# main.net
KiCad netlist of a schematic drawn in EAGLE
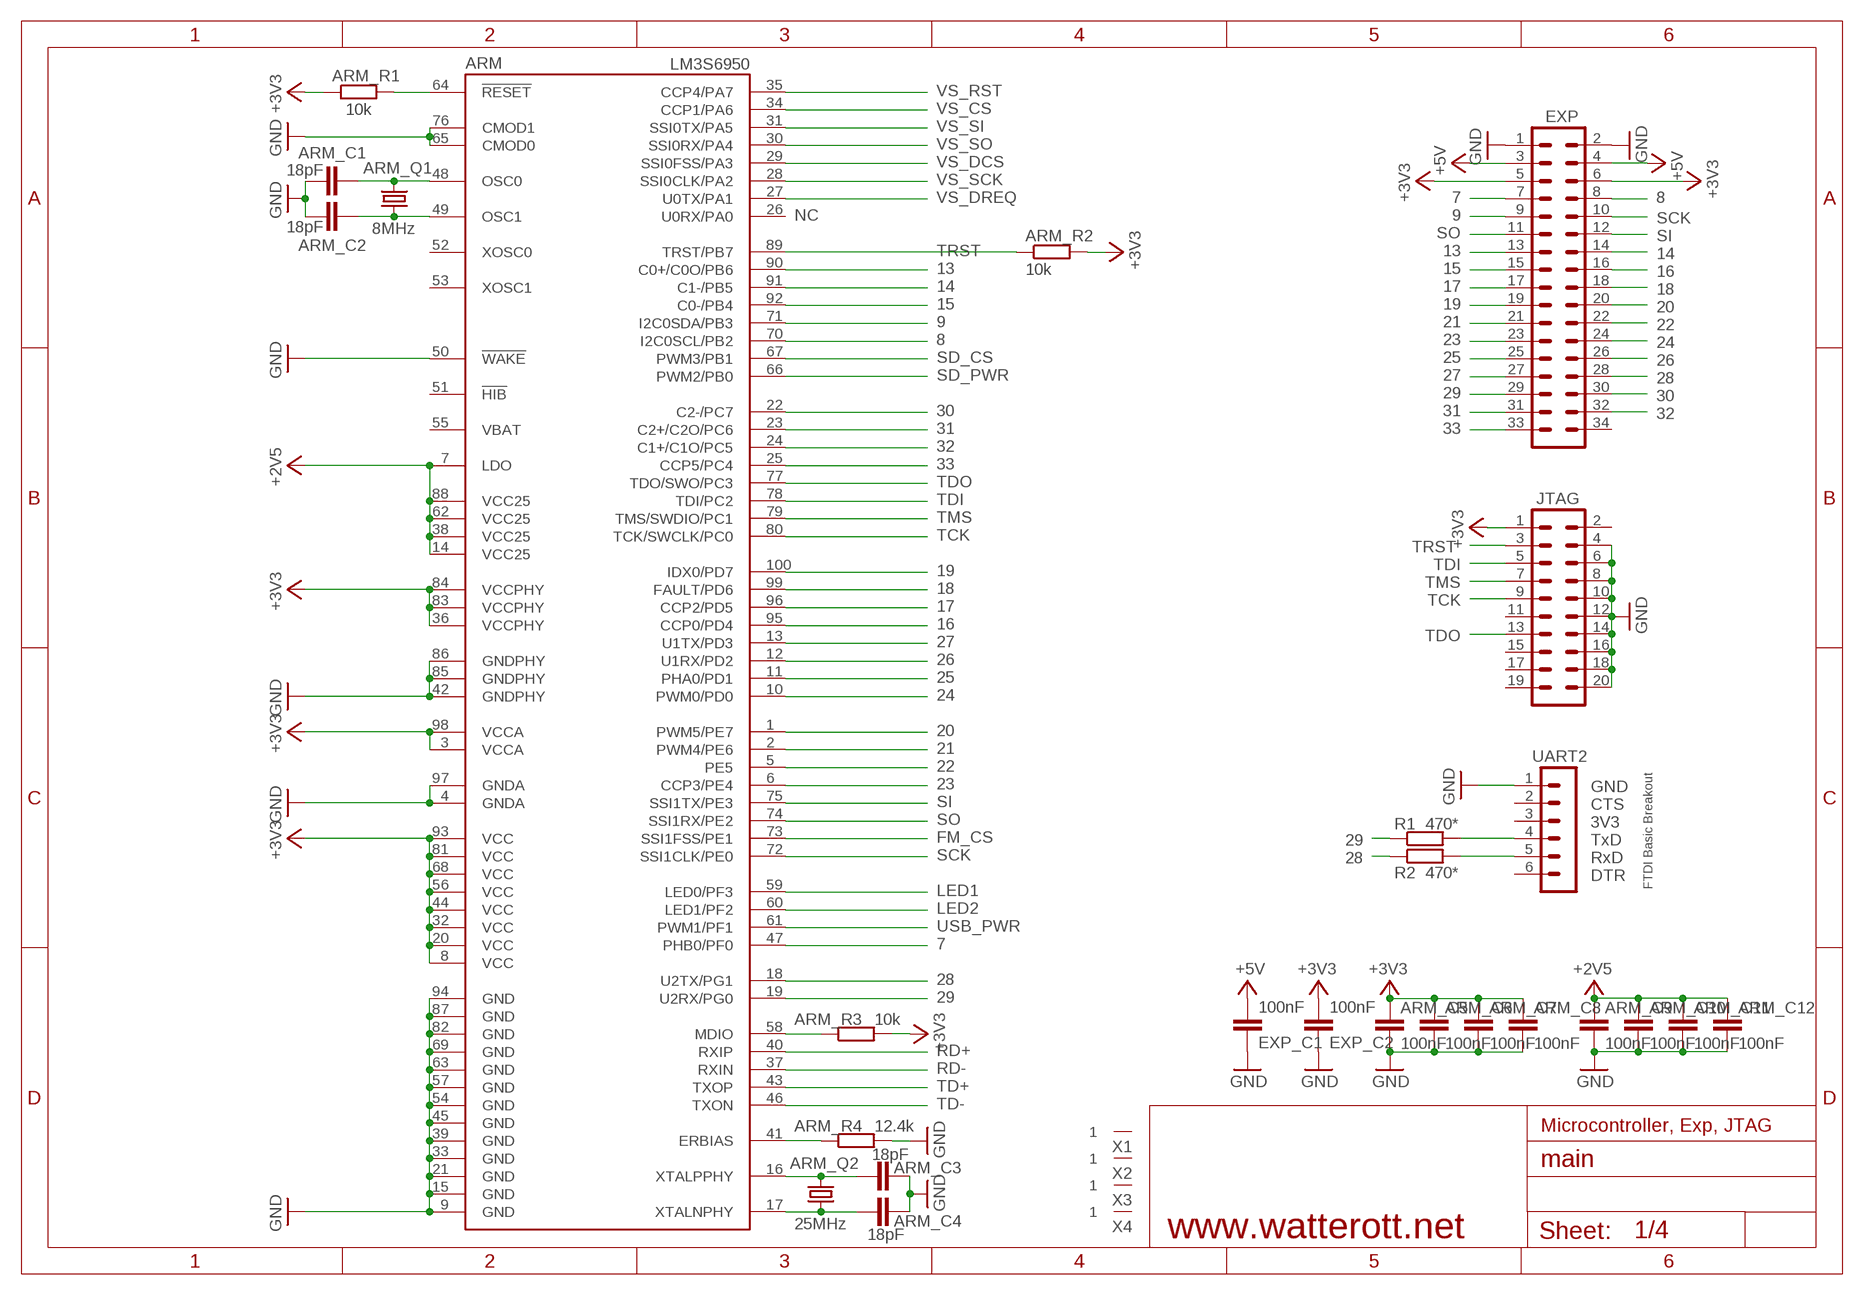
[diagram p0: schematic, sheet 1]
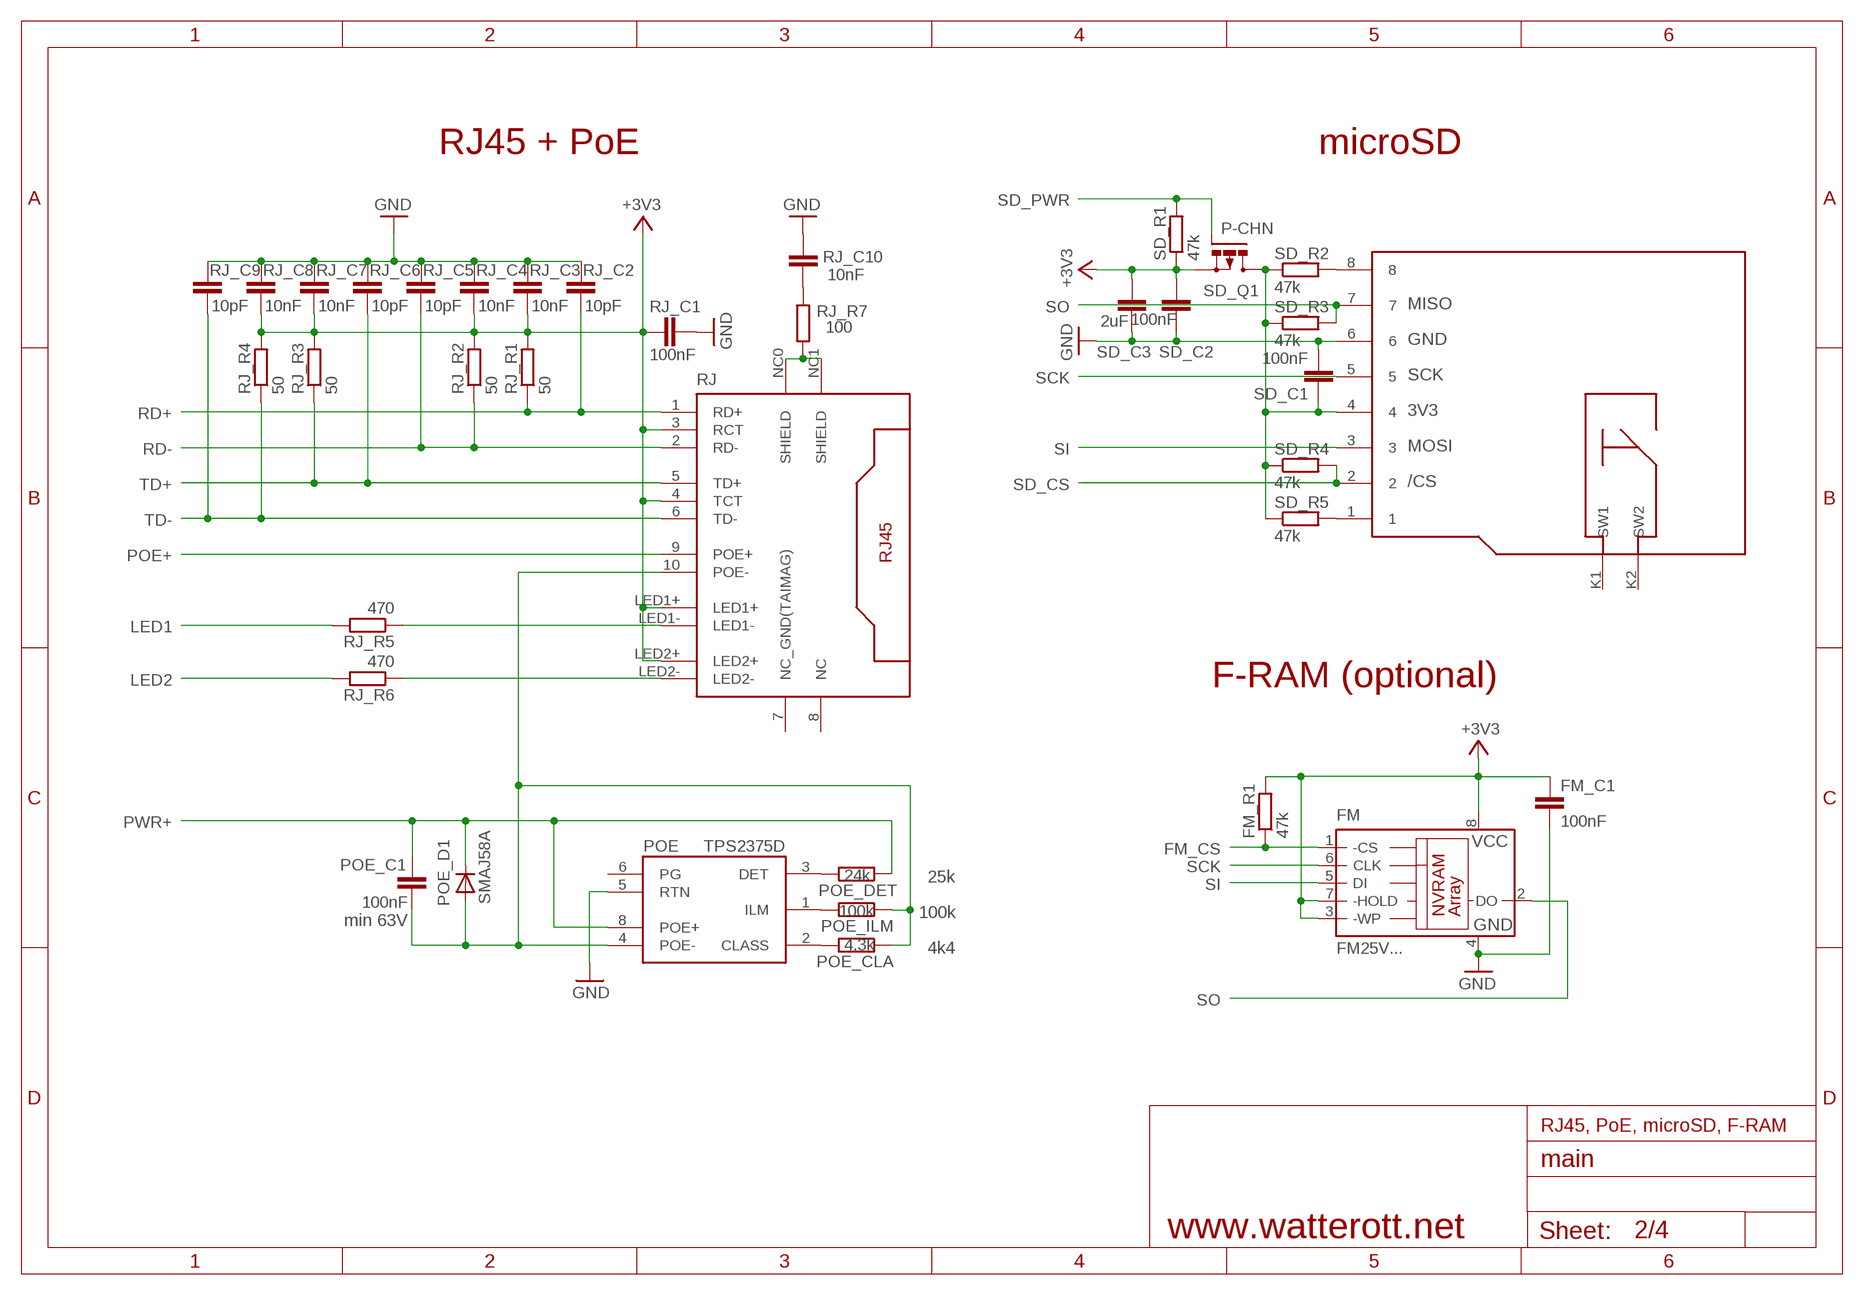
[diagram p1: schematic, sheet 2]
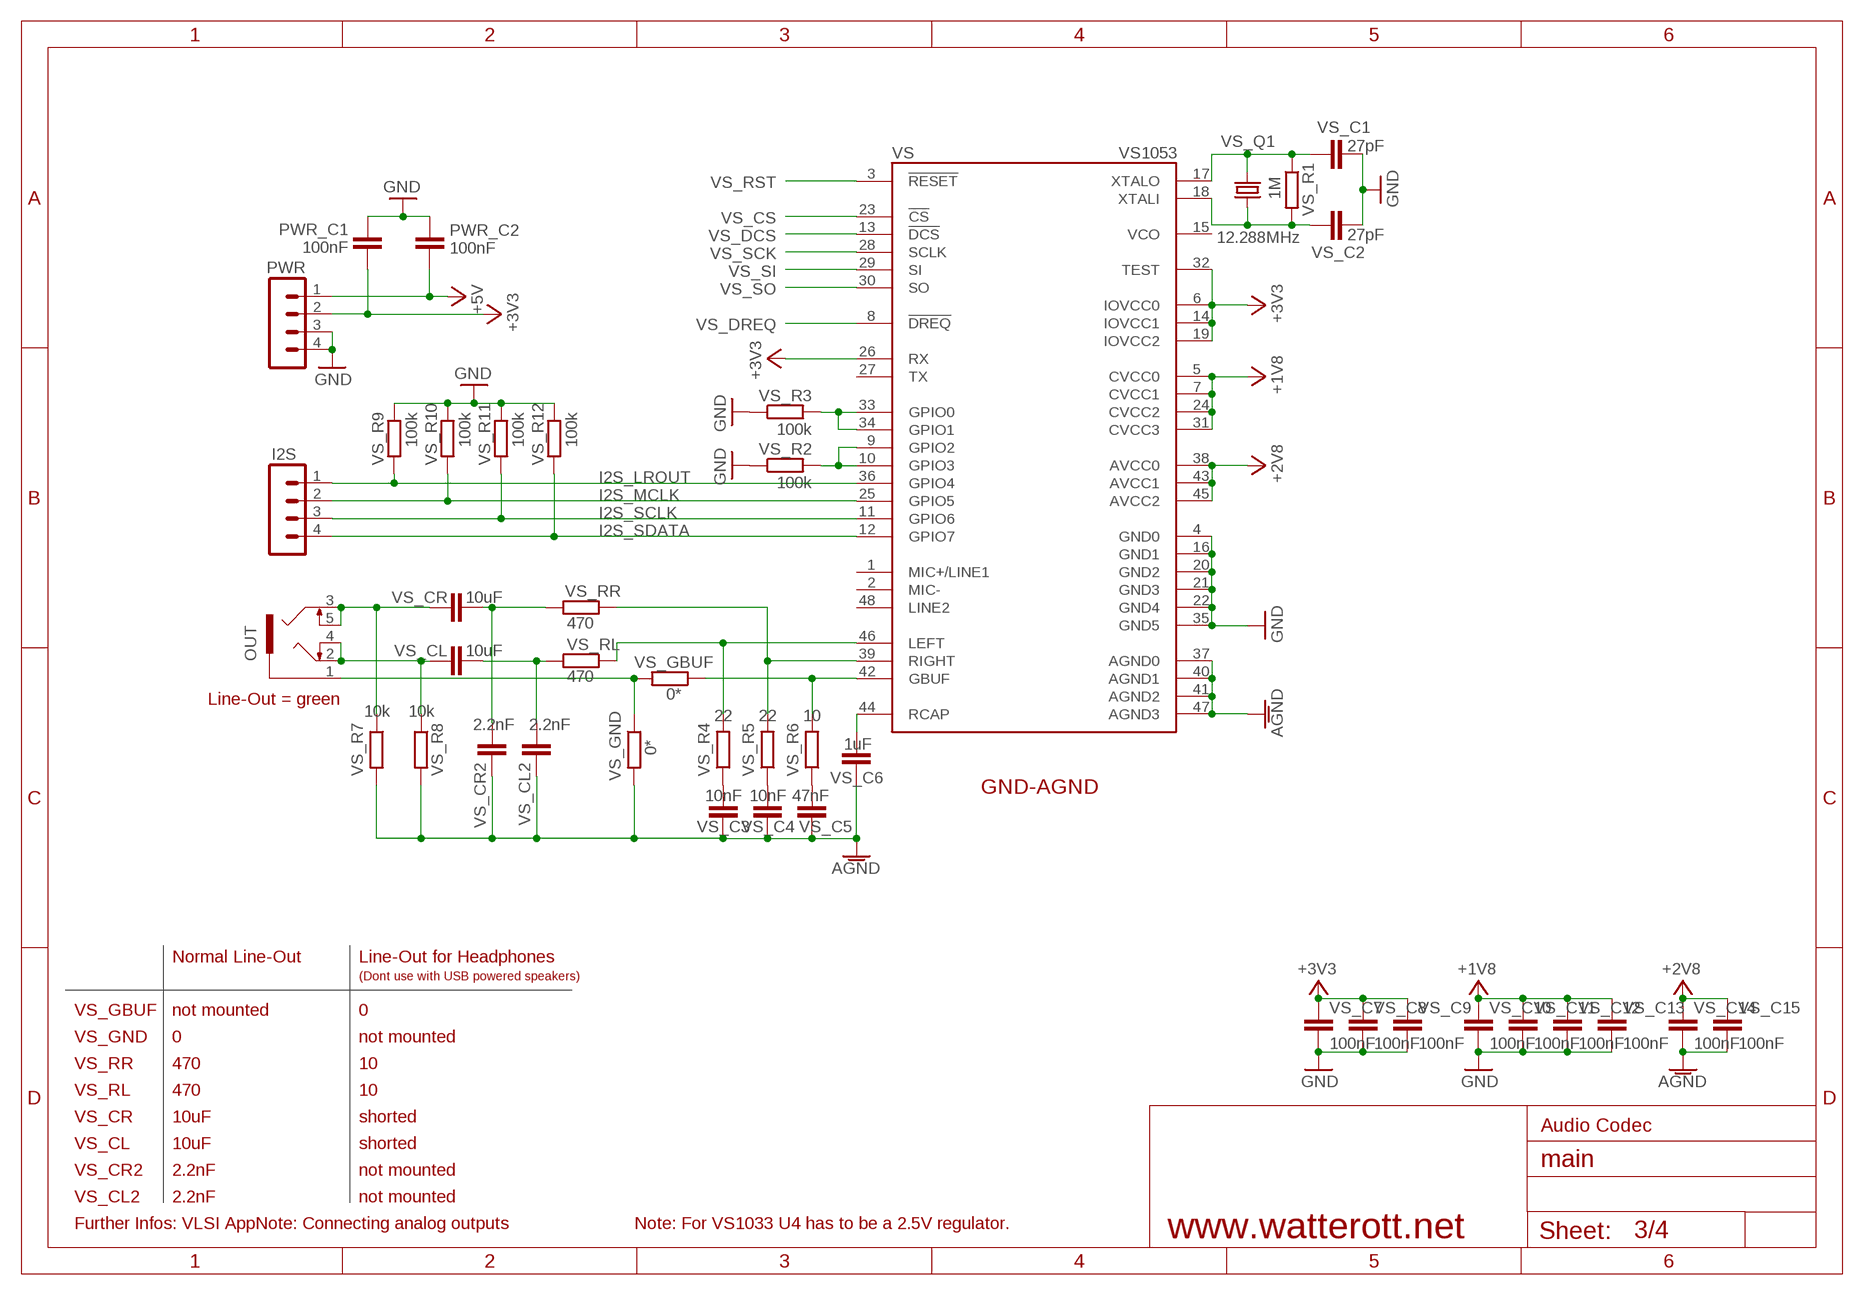
[diagram p2: schematic, sheet 3]
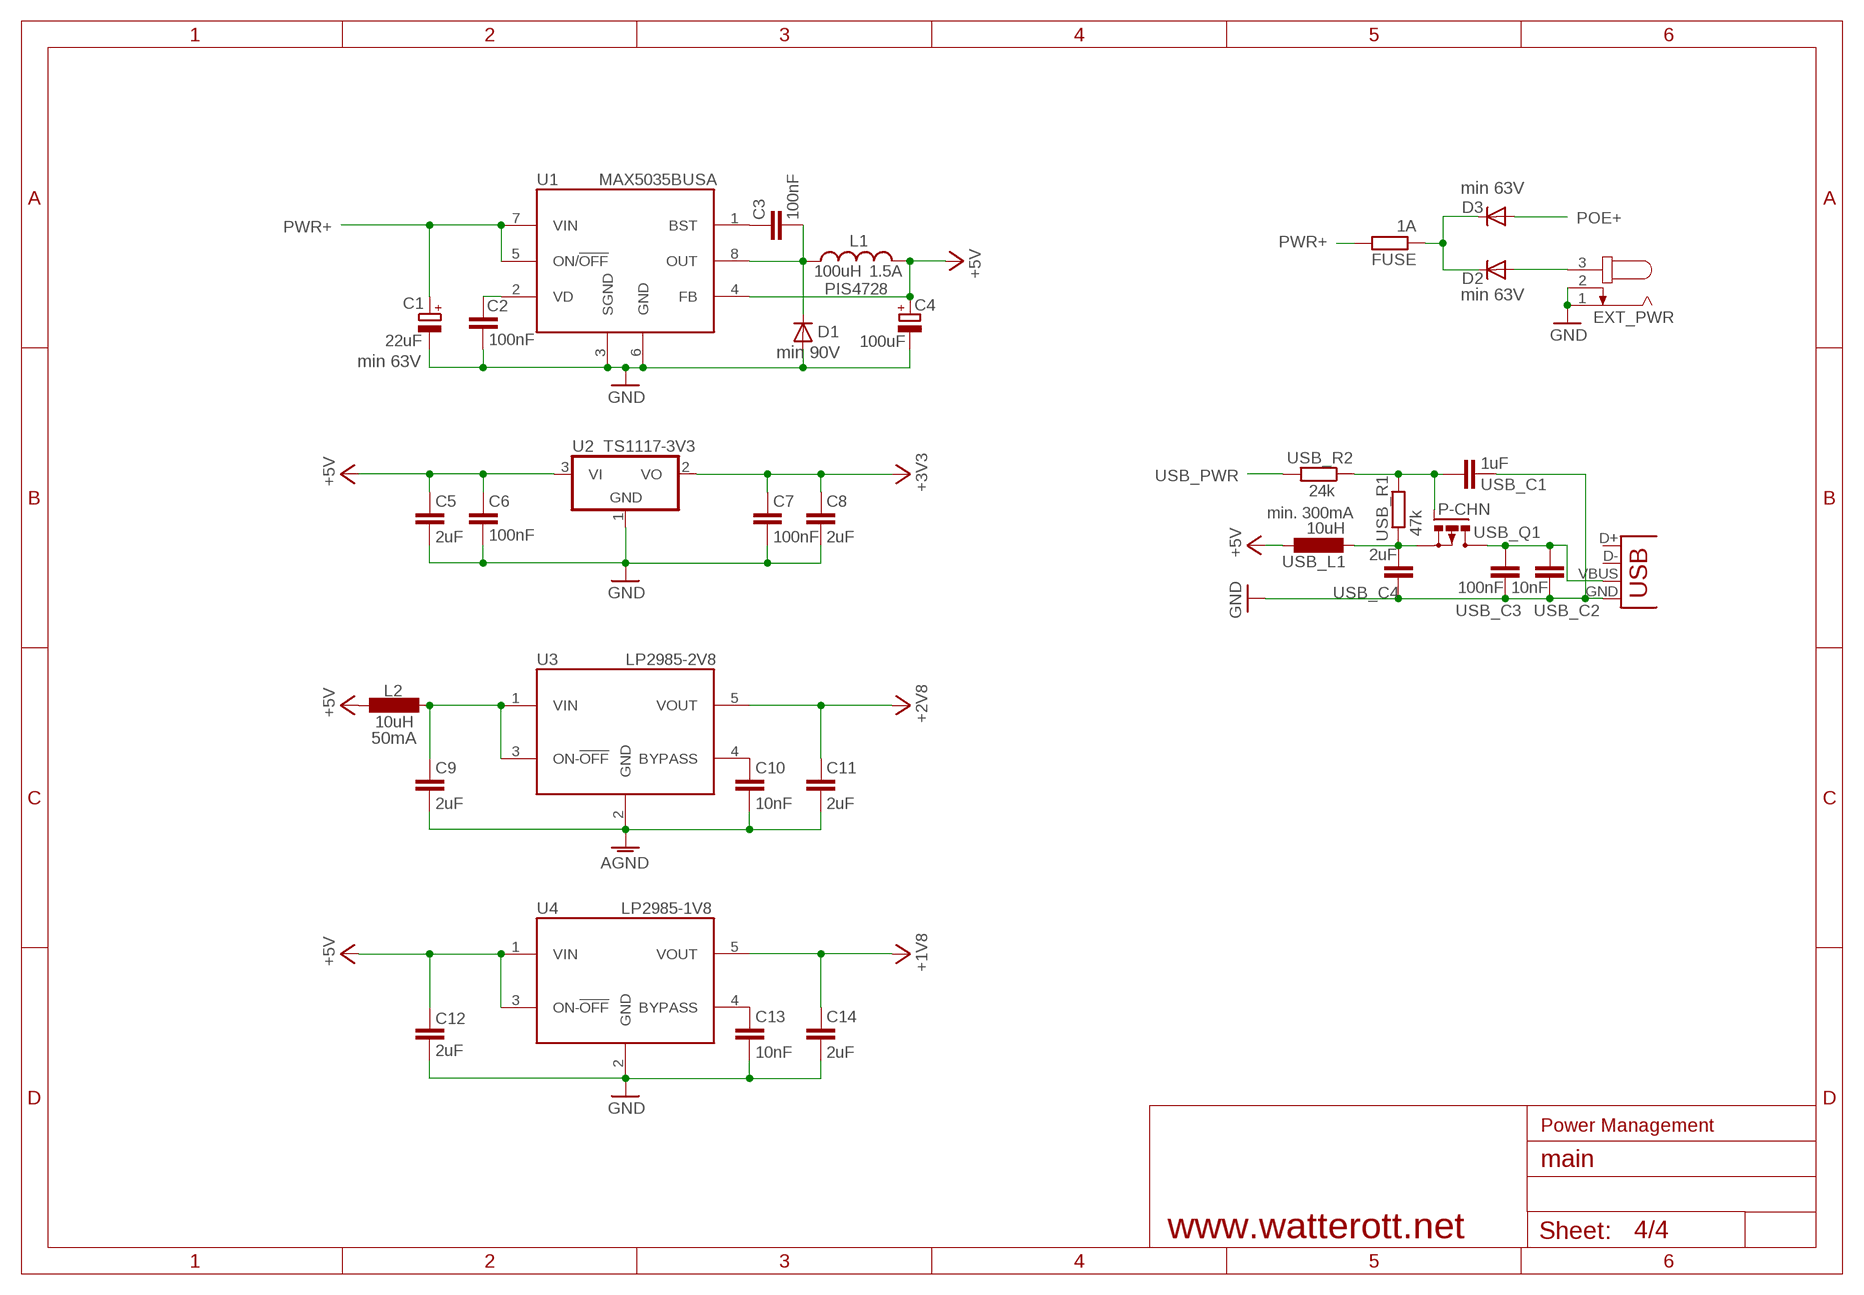
[diagram p3: schematic, sheet 4]

(export (version "E")
  (design (tool "Eeschema 10.0.6"))
  (components
    (comp (ref "I2S")
      (value "MA04-1")
      (footprint "eagle-import:MA04-1")
      (libsource (lib "eagle-import") (part "MA04-1"))
    )
    (comp (ref "OUT")
      (value "1503_09")
      (footprint "eagle-import:1503_09")
      (libsource (lib "eagle-import") (part "1503_09"))
    )
    (comp (ref "PWR")
      (value "MA04-1")
      (footprint "eagle-import:MA04-1")
      (libsource (lib "eagle-import") (part "MA04-1"))
    )
    (comp (ref "PWR_C1")
      (value "100nF")
      (footprint "eagle-import:C0603")
      (libsource (lib "eagle-import") (part "C-EUC0603"))
    )
    (comp (ref "PWR_C2")
      (value "100nF")
      (footprint "eagle-import:C0603")
      (libsource (lib "eagle-import") (part "C-EUC0603"))
    )
    (comp (ref "VS")
      (value "VS1053")
      (footprint "eagle-import:LQFP-48")
      (libsource (lib "eagle-import") (part "VS1053"))
    )
    (comp (ref "VS_C1")
      (value "27pF")
      (footprint "eagle-import:C0603")
      (libsource (lib "eagle-import") (part "C-EUC0603"))
    )
    (comp (ref "VS_C2")
      (value "27pF")
      (footprint "eagle-import:C0603")
      (libsource (lib "eagle-import") (part "C-EUC0603"))
    )
    (comp (ref "VS_C3")
      (value "10nF")
      (footprint "eagle-import:C0603")
      (libsource (lib "eagle-import") (part "C-EUC0603"))
    )
    (comp (ref "VS_C4")
      (value "10nF")
      (footprint "eagle-import:C0603")
      (libsource (lib "eagle-import") (part "C-EUC0603"))
    )
    (comp (ref "VS_C5")
      (value "47nF")
      (footprint "eagle-import:C0603")
      (libsource (lib "eagle-import") (part "C-EUC0603"))
    )
    (comp (ref "VS_C6")
      (value "1uF")
      (footprint "eagle-import:C0603")
      (libsource (lib "eagle-import") (part "C-EUC0603"))
    )
    (comp (ref "VS_C7")
      (value "100nF")
      (footprint "eagle-import:C0603")
      (libsource (lib "eagle-import") (part "C-EUC0603"))
    )
    (comp (ref "VS_C8")
      (value "100nF")
      (footprint "eagle-import:C0603")
      (libsource (lib "eagle-import") (part "C-EUC0603"))
    )
    (comp (ref "VS_C9")
      (value "100nF")
      (footprint "eagle-import:C0603")
      (libsource (lib "eagle-import") (part "C-EUC0603"))
    )
    (comp (ref "VS_C10")
      (value "100nF")
      (footprint "eagle-import:C0603")
      (libsource (lib "eagle-import") (part "C-EUC0603"))
    )
    (comp (ref "VS_C11")
      (value "100nF")
      (footprint "eagle-import:C0603")
      (libsource (lib "eagle-import") (part "C-EUC0603"))
    )
    (comp (ref "VS_C12")
      (value "100nF")
      (footprint "eagle-import:C0603")
      (libsource (lib "eagle-import") (part "C-EUC0603"))
    )
    (comp (ref "VS_C13")
      (value "100nF")
      (footprint "eagle-import:C0603")
      (libsource (lib "eagle-import") (part "C-EUC0603"))
    )
    (comp (ref "VS_C14")
      (value "100nF")
      (footprint "eagle-import:C0603")
      (libsource (lib "eagle-import") (part "C-EUC0603"))
    )
    (comp (ref "VS_C15")
      (value "100nF")
      (footprint "eagle-import:C0603")
      (libsource (lib "eagle-import") (part "C-EUC0603"))
    )
    (comp (ref "VS_CL")
      (value "10uF")
      (footprint "eagle-import:C1210")
      (libsource (lib "eagle-import") (part "C-EUC1210"))
    )
    (comp (ref "VS_CL2")
      (value "2.2nF")
      (footprint "eagle-import:C0603")
      (libsource (lib "eagle-import") (part "C-EUC0603"))
    )
    (comp (ref "VS_CR")
      (value "10uF")
      (footprint "eagle-import:C1210")
      (libsource (lib "eagle-import") (part "C-EUC1210"))
    )
    (comp (ref "VS_CR2")
      (value "2.2nF")
      (footprint "eagle-import:C0603")
      (libsource (lib "eagle-import") (part "C-EUC0603"))
    )
    (comp (ref "VS_GBUF")
      (value "0*")
      (footprint "eagle-import:R0603")
      (libsource (lib "eagle-import") (part "R-EU_R0603"))
    )
    (comp (ref "VS_GND")
      (value "0*")
      (footprint "eagle-import:R0603")
      (libsource (lib "eagle-import") (part "R-EU_R0603"))
    )
    (comp (ref "VS_Q1")
      (value "12.288MHz")
      (footprint "eagle-import:SM49")
      (libsource (lib "eagle-import") (part "CRYSTALSM49"))
    )
    (comp (ref "VS_R1")
      (value "1M")
      (footprint "eagle-import:R0603")
      (libsource (lib "eagle-import") (part "R-EU_R0603"))
    )
    (comp (ref "VS_R2")
      (value "100k")
      (footprint "eagle-import:R0603")
      (libsource (lib "eagle-import") (part "R-EU_R0603"))
    )
    (comp (ref "VS_R3")
      (value "100k")
      (footprint "eagle-import:R0603")
      (libsource (lib "eagle-import") (part "R-EU_R0603"))
    )
    (comp (ref "VS_R4")
      (value "22")
      (footprint "eagle-import:R0603")
      (libsource (lib "eagle-import") (part "R-EU_R0603"))
    )
    (comp (ref "VS_R5")
      (value "22")
      (footprint "eagle-import:R0603")
      (libsource (lib "eagle-import") (part "R-EU_R0603"))
    )
    (comp (ref "VS_R6")
      (value "10")
      (footprint "eagle-import:R0603")
      (libsource (lib "eagle-import") (part "R-EU_R0603"))
    )
    (comp (ref "VS_R7")
      (value "10k")
      (footprint "eagle-import:R0603")
      (libsource (lib "eagle-import") (part "R-EU_R0603"))
    )
    (comp (ref "VS_R8")
      (value "10k")
      (footprint "eagle-import:R0603")
      (libsource (lib "eagle-import") (part "R-EU_R0603"))
    )
    (comp (ref "VS_R9")
      (value "100k")
      (footprint "eagle-import:R0603")
      (libsource (lib "eagle-import") (part "R-EU_R0603"))
    )
    (comp (ref "VS_R10")
      (value "100k")
      (footprint "eagle-import:R0603")
      (libsource (lib "eagle-import") (part "R-EU_R0603"))
    )
    (comp (ref "VS_R11")
      (value "100k")
      (footprint "eagle-import:R0603")
      (libsource (lib "eagle-import") (part "R-EU_R0603"))
    )
    (comp (ref "VS_R12")
      (value "100k")
      (footprint "eagle-import:R0603")
      (libsource (lib "eagle-import") (part "R-EU_R0603"))
    )
    (comp (ref "VS_RL")
      (value "470")
      (footprint "eagle-import:R0603")
      (libsource (lib "eagle-import") (part "R-EU_R0603"))
    )
    (comp (ref "VS_RR")
      (value "470")
      (footprint "eagle-import:R0603")
      (libsource (lib "eagle-import") (part "R-EU_R0603"))
    )
    (comp (ref "FM")
      (value "FM25V...")
      (footprint "eagle-import:SO8")
      (libsource (lib "eagle-import") (part "FM25-S"))
    )
    (comp (ref "FM_C1")
      (value "100nF")
      (footprint "eagle-import:C0603")
      (libsource (lib "eagle-import") (part "C-EUC0603"))
    )
    (comp (ref "FM_R1")
      (value "47k")
      (footprint "eagle-import:R0603")
      (libsource (lib "eagle-import") (part "R-EU_R0603"))
    )
    (comp (ref "POE")
      (value "TPS2375D")
      (footprint "eagle-import:SO08")
      (libsource (lib "eagle-import") (part "TPS237X"))
    )
    (comp (ref "POE_C1")
      (value "100nF")
      (footprint "eagle-import:C1206")
      (fields (field (name "VOLTAGE") "min 63V"))
      (libsource (lib "eagle-import") (part "C-EUC1206"))
    )
    (comp (ref "POE_CLA")
      (value "4,3k")
      (footprint "eagle-import:R0603")
      (libsource (lib "eagle-import") (part "R-EU_R0603"))
    )
    (comp (ref "POE_D1")
      (value "SMAJ58A")
      (footprint "eagle-import:DO214AA")
      (libsource (lib "eagle-import") (part "DIODE-DO214AA"))
    )
    (comp (ref "POE_DET")
      (value "24k")
      (footprint "eagle-import:R0603")
      (libsource (lib "eagle-import") (part "R-EU_R0603"))
    )
    (comp (ref "POE_ILM")
      (value "100k")
      (footprint "eagle-import:R0603")
      (libsource (lib "eagle-import") (part "R-EU_R0603"))
    )
    (comp (ref "RJ")
      (value "RJ45-8-POEWE")
      (footprint "eagle-import:WE_POE")
      (libsource (lib "eagle-import") (part "RJ45-8-POEWE"))
    )
    (comp (ref "RJ_C1")
      (value "100nF")
      (footprint "eagle-import:C0603")
      (libsource (lib "eagle-import") (part "C-EUC0603"))
    )
    (comp (ref "RJ_C2")
      (value "10pF")
      (footprint "eagle-import:C0603")
      (libsource (lib "eagle-import") (part "C-EUC0603"))
    )
    (comp (ref "RJ_C3")
      (value "10nF")
      (footprint "eagle-import:C0603")
      (libsource (lib "eagle-import") (part "C-EUC0603"))
    )
    (comp (ref "RJ_C4")
      (value "10nF")
      (footprint "eagle-import:C0603")
      (libsource (lib "eagle-import") (part "C-EUC0603"))
    )
    (comp (ref "RJ_C5")
      (value "10pF")
      (footprint "eagle-import:C0603")
      (libsource (lib "eagle-import") (part "C-EUC0603"))
    )
    (comp (ref "RJ_C6")
      (value "10pF")
      (footprint "eagle-import:C0603")
      (libsource (lib "eagle-import") (part "C-EUC0603"))
    )
    (comp (ref "RJ_C7")
      (value "10nF")
      (footprint "eagle-import:C0603")
      (libsource (lib "eagle-import") (part "C-EUC0603"))
    )
    (comp (ref "RJ_C8")
      (value "10nF")
      (footprint "eagle-import:C0603")
      (libsource (lib "eagle-import") (part "C-EUC0603"))
    )
    (comp (ref "RJ_C9")
      (value "10pF")
      (footprint "eagle-import:C0603")
      (libsource (lib "eagle-import") (part "C-EUC0603"))
    )
    (comp (ref "RJ_C10")
      (value "10nF")
      (footprint "eagle-import:C0603")
      (libsource (lib "eagle-import") (part "C-EUC0603"))
    )
    (comp (ref "RJ_R1")
      (value "50")
      (footprint "eagle-import:R0603")
      (libsource (lib "eagle-import") (part "R-EU_R0603"))
    )
    (comp (ref "RJ_R2")
      (value "50")
      (footprint "eagle-import:R0603")
      (libsource (lib "eagle-import") (part "R-EU_R0603"))
    )
    (comp (ref "RJ_R3")
      (value "50")
      (footprint "eagle-import:R0603")
      (libsource (lib "eagle-import") (part "R-EU_R0603"))
    )
    (comp (ref "RJ_R4")
      (value "50")
      (footprint "eagle-import:R0603")
      (libsource (lib "eagle-import") (part "R-EU_R0603"))
    )
    (comp (ref "RJ_R5")
      (value "470")
      (footprint "eagle-import:R0603")
      (libsource (lib "eagle-import") (part "R-EU_R0603"))
    )
    (comp (ref "RJ_R6")
      (value "470")
      (footprint "eagle-import:R0603")
      (libsource (lib "eagle-import") (part "R-EU_R0603"))
    )
    (comp (ref "RJ_R7")
      (value "100")
      (footprint "eagle-import:R0603")
      (libsource (lib "eagle-import") (part "R-EU_R0603"))
    )
    (comp (ref "SD")
      (value "MICRO-SD")
      (footprint "eagle-import:MICRO-SD")
      (libsource (lib "eagle-import") (part "MICRO-SD"))
    )
    (comp (ref "SD_C1")
      (value "100nF")
      (footprint "eagle-import:C0603")
      (libsource (lib "eagle-import") (part "C-EUC0603"))
    )
    (comp (ref "SD_C2")
      (value "100nF")
      (footprint "eagle-import:C0603")
      (libsource (lib "eagle-import") (part "C-EUC0603"))
    )
    (comp (ref "SD_C3")
      (value "2uF")
      (footprint "eagle-import:C0603")
      (libsource (lib "eagle-import") (part "C-EUC0603"))
    )
    (comp (ref "SD_Q1")
      (value "P-CHN")
      (footprint "eagle-import:MICRO3")
      (libsource (lib "eagle-import") (part "IRLML6402"))
    )
    (comp (ref "SD_R1")
      (value "47k")
      (footprint "eagle-import:R0603")
      (libsource (lib "eagle-import") (part "R-EU_R0603"))
    )
    (comp (ref "SD_R2")
      (value "47k")
      (footprint "eagle-import:R0603")
      (libsource (lib "eagle-import") (part "R-EU_R0603"))
    )
    (comp (ref "SD_R3")
      (value "47k")
      (footprint "eagle-import:R0603")
      (libsource (lib "eagle-import") (part "R-EU_R0603"))
    )
    (comp (ref "SD_R4")
      (value "47k")
      (footprint "eagle-import:R0603")
      (libsource (lib "eagle-import") (part "R-EU_R0603"))
    )
    (comp (ref "SD_R5")
      (value "47k")
      (footprint "eagle-import:R0603")
      (libsource (lib "eagle-import") (part "R-EU_R0603"))
    )
    (comp (ref "C1")
      (value "22uF")
      (footprint "eagle-import:153CLV-0810")
      (fields (field (name "VOLTAGE") "min 63V"))
      (libsource (lib "eagle-import") (part "CPOL-EU153CLV-0810"))
    )
    (comp (ref "C2")
      (value "100nF")
      (footprint "eagle-import:C0603")
      (libsource (lib "eagle-import") (part "C-EUC0603"))
    )
    (comp (ref "C3")
      (value "100nF")
      (footprint "eagle-import:C0603")
      (libsource (lib "eagle-import") (part "C-EUC0603"))
    )
    (comp (ref "C4")
      (value "100uF")
      (footprint "eagle-import:153CLV-0810")
      (libsource (lib "eagle-import") (part "CPOL-EU153CLV-0810"))
    )
    (comp (ref "C5")
      (value "2uF")
      (footprint "eagle-import:C0603")
      (libsource (lib "eagle-import") (part "C-EUC0603"))
    )
    (comp (ref "C6")
      (value "100nF")
      (footprint "eagle-import:C0603")
      (libsource (lib "eagle-import") (part "C-EUC0603"))
    )
    (comp (ref "C7")
      (value "100nF")
      (footprint "eagle-import:C0603")
      (libsource (lib "eagle-import") (part "C-EUC0603"))
    )
    (comp (ref "C8")
      (value "2uF")
      (footprint "eagle-import:C0603")
      (libsource (lib "eagle-import") (part "C-EUC0603"))
    )
    (comp (ref "C9")
      (value "2uF")
      (footprint "eagle-import:C0603")
      (libsource (lib "eagle-import") (part "C-EUC0603"))
    )
    (comp (ref "C10")
      (value "10nF")
      (footprint "eagle-import:C0603")
      (libsource (lib "eagle-import") (part "C-EUC0603"))
    )
    (comp (ref "C11")
      (value "2uF")
      (footprint "eagle-import:C0603")
      (libsource (lib "eagle-import") (part "C-EUC0603"))
    )
    (comp (ref "C12")
      (value "2uF")
      (footprint "eagle-import:C0603")
      (libsource (lib "eagle-import") (part "C-EUC0603"))
    )
    (comp (ref "C13")
      (value "10nF")
      (footprint "eagle-import:C0603")
      (libsource (lib "eagle-import") (part "C-EUC0603"))
    )
    (comp (ref "C14")
      (value "2uF")
      (footprint "eagle-import:C0603")
      (libsource (lib "eagle-import") (part "C-EUC0603"))
    )
    (comp (ref "D1")
      (value "DIODE-DO214AA")
      (footprint "eagle-import:DO214AA")
      (fields (field (name "VOLTAGE") "min 90V"))
      (libsource (lib "eagle-import") (part "DIODE-DO214AA"))
    )
    (comp (ref "D2")
      (value "DIODE-DO214AA")
      (footprint "eagle-import:DO214AA")
      (fields (field (name "VOLTAGE") "min 63V"))
      (libsource (lib "eagle-import") (part "DIODE-DO214AA"))
    )
    (comp (ref "D3")
      (value "DIODE-DO214AA")
      (footprint "eagle-import:DO214AA")
      (fields (field (name "VOLTAGE") "min 63V"))
      (libsource (lib "eagle-import") (part "DIODE-DO214AA"))
    )
    (comp (ref "EXT_PWR")
      (value "JACK-PLUG0")
      (footprint "eagle-import:SPC4077")
      (libsource (lib "eagle-import") (part "JACK-PLUG0"))
    )
    (comp (ref "FUSE")
      (value "1A")
      (footprint "eagle-import:R1206")
      (libsource (lib "eagle-import") (part "R-EU_R1206"))
    )
    (comp (ref "L1")
      (value "100uH")
      (footprint "eagle-import:CDRH")
      (libsource (lib "eagle-import") (part "INDUCTORCDRH"))
    )
    (comp (ref "L2")
      (value "10uH")
      (footprint "eagle-import:L3230M")
      (fields (field (name "CURRENT") "50mA"))
      (libsource (lib "eagle-import") (part "L-EUL3230M"))
    )
    (comp (ref "U1")
      (value "MAX5035BUSA")
      (footprint "eagle-import:SO8")
      (libsource (lib "eagle-import") (part "MAX5035"))
    )
    (comp (ref "U2")
      (value "TS1117-3V3")
      (footprint "eagle-import:SOT223")
      (libsource (lib "eagle-import") (part "TS1117"))
    )
    (comp (ref "U3")
      (value "LP2985-2V8")
      (footprint "eagle-import:SOT23-5")
      (libsource (lib "eagle-import") (part "LP2985"))
    )
    (comp (ref "U4")
      (value "LP2985-1V8")
      (footprint "eagle-import:SOT23-5")
      (libsource (lib "eagle-import") (part "LP2985"))
    )
    (comp (ref "USB")
      (value "USB-A-S")
      (footprint "eagle-import:USB-A-S")
      (libsource (lib "eagle-import") (part "USB-A-S"))
    )
    (comp (ref "USB_C1")
      (value "1uF")
      (footprint "eagle-import:C0603")
      (libsource (lib "eagle-import") (part "C-EUC0603"))
    )
    (comp (ref "USB_C2")
      (value "10nF")
      (footprint "eagle-import:C0603")
      (libsource (lib "eagle-import") (part "C-EUC0603"))
    )
    (comp (ref "USB_C3")
      (value "100nF")
      (footprint "eagle-import:C0603")
      (libsource (lib "eagle-import") (part "C-EUC0603"))
    )
    (comp (ref "USB_C4")
      (value "2uF")
      (footprint "eagle-import:C0805")
      (libsource (lib "eagle-import") (part "C-EUC0805"))
    )
    (comp (ref "USB_L1")
      (value "10uH")
      (footprint "eagle-import:L3230M")
      (fields (field (name "CURRENT") "min. 300mA"))
      (libsource (lib "eagle-import") (part "L-EUL3230M"))
    )
    (comp (ref "USB_Q1")
      (value "P-CHN")
      (footprint "eagle-import:MICRO3")
      (libsource (lib "eagle-import") (part "IRLML6402"))
    )
    (comp (ref "USB_R1")
      (value "47k")
      (footprint "eagle-import:R0603")
      (libsource (lib "eagle-import") (part "R-EU_R0603"))
    )
    (comp (ref "USB_R2")
      (value "24k")
      (footprint "eagle-import:R0603")
      (libsource (lib "eagle-import") (part "R-EU_R0603"))
    )
    (comp (ref "ARM")
      (value "LM3S6950")
      (footprint "eagle-import:LQFP100")
      (libsource (lib "eagle-import") (part "LM3S6950"))
    )
    (comp (ref "ARM_C1")
      (value "18pF")
      (footprint "eagle-import:C0603")
      (libsource (lib "eagle-import") (part "C-EUC0603"))
    )
    (comp (ref "ARM_C2")
      (value "18pF")
      (footprint "eagle-import:C0603")
      (libsource (lib "eagle-import") (part "C-EUC0603"))
    )
    (comp (ref "ARM_C3")
      (value "18pF")
      (footprint "eagle-import:C0603")
      (libsource (lib "eagle-import") (part "C-EUC0603"))
    )
    (comp (ref "ARM_C4")
      (value "18pF")
      (footprint "eagle-import:C0603")
      (libsource (lib "eagle-import") (part "C-EUC0603"))
    )
    (comp (ref "ARM_C5")
      (value "100nF")
      (footprint "eagle-import:C0603")
      (libsource (lib "eagle-import") (part "C-EUC0603"))
    )
    (comp (ref "ARM_C6")
      (value "100nF")
      (footprint "eagle-import:C0603")
      (libsource (lib "eagle-import") (part "C-EUC0603"))
    )
    (comp (ref "ARM_C7")
      (value "100nF")
      (footprint "eagle-import:C0603")
      (libsource (lib "eagle-import") (part "C-EUC0603"))
    )
    (comp (ref "ARM_C8")
      (value "100nF")
      (footprint "eagle-import:C0603")
      (libsource (lib "eagle-import") (part "C-EUC0603"))
    )
    (comp (ref "ARM_C9")
      (value "100nF")
      (footprint "eagle-import:C0603")
      (libsource (lib "eagle-import") (part "C-EUC0603"))
    )
    (comp (ref "ARM_C10")
      (value "100nF")
      (footprint "eagle-import:C0603")
      (libsource (lib "eagle-import") (part "C-EUC0603"))
    )
    (comp (ref "ARM_C11")
      (value "100nF")
      (footprint "eagle-import:C0603")
      (libsource (lib "eagle-import") (part "C-EUC0603"))
    )
    (comp (ref "ARM_C12")
      (value "100nF")
      (footprint "eagle-import:C0603")
      (libsource (lib "eagle-import") (part "C-EUC0603"))
    )
    (comp (ref "ARM_Q1")
      (value "8MHz")
      (footprint "eagle-import:CS10")
      (libsource (lib "eagle-import") (part "CRYSTALCS10"))
    )
    (comp (ref "ARM_Q2")
      (value "25MHz")
      (footprint "eagle-import:CS10")
      (libsource (lib "eagle-import") (part "CRYSTALCS10"))
    )
    (comp (ref "ARM_R1")
      (value "10k")
      (footprint "eagle-import:R0603")
      (libsource (lib "eagle-import") (part "R-EU_R0603"))
    )
    (comp (ref "ARM_R2")
      (value "10k")
      (footprint "eagle-import:R0603")
      (libsource (lib "eagle-import") (part "R-EU_R0603"))
    )
    (comp (ref "ARM_R3")
      (value "10k")
      (footprint "eagle-import:R0603")
      (libsource (lib "eagle-import") (part "R-EU_R0603"))
    )
    (comp (ref "ARM_R4")
      (value "12.4k")
      (footprint "eagle-import:R0603")
      (libsource (lib "eagle-import") (part "R-EU_R0603"))
    )
    (comp (ref "EXP")
      (value "MA17-2")
      (footprint "eagle-import:MA17-2")
      (libsource (lib "eagle-import") (part "MA17-2"))
    )
    (comp (ref "EXP_C1")
      (value "100nF")
      (footprint "eagle-import:C0603")
      (libsource (lib "eagle-import") (part "C-EUC0603"))
    )
    (comp (ref "EXP_C2")
      (value "100nF")
      (footprint "eagle-import:C0603")
      (libsource (lib "eagle-import") (part "C-EUC0603"))
    )
    (comp (ref "JTAG")
      (value "MA10-2SMD")
      (footprint "eagle-import:MA10-2_SMD")
      (libsource (lib "eagle-import") (part "MA10-2SMD"))
    )
    (comp (ref "R1")
      (value "470*")
      (footprint "eagle-import:R0603")
      (libsource (lib "eagle-import") (part "R-EU_R0603"))
    )
    (comp (ref "R2")
      (value "470*")
      (footprint "eagle-import:R0603")
      (libsource (lib "eagle-import") (part "R-EU_R0603"))
    )
    (comp (ref "UART2")
      (value "MA06-1")
      (footprint "eagle-import:MA06-1")
      (libsource (lib "eagle-import") (part "MA06-1"))
    )
    (comp (ref "X1")
      (value "ELLIPTICAL-PADS")
      (footprint "eagle-import:SMD-ELLIPSE")
      (libsource (lib "eagle-import") (part "ELLIPTICAL-PADS"))
    )
    (comp (ref "X2")
      (value "ELLIPTICAL-PADS")
      (footprint "eagle-import:SMD-ELLIPSE")
      (libsource (lib "eagle-import") (part "ELLIPTICAL-PADS"))
    )
    (comp (ref "X3")
      (value "ELLIPTICAL-PADS")
      (footprint "eagle-import:SMD-ELLIPSE")
      (libsource (lib "eagle-import") (part "ELLIPTICAL-PADS"))
    )
    (comp (ref "X4")
      (value "ELLIPTICAL-PADS")
      (footprint "eagle-import:SMD-ELLIPSE")
      (libsource (lib "eagle-import") (part "ELLIPTICAL-PADS"))
    )
  )
  (nets
    (net (code "1") (name "+1V8") (class "Default")
      (node (ref "C14") (pin "1") (pinfunction "1_1") (pintype "passive"))
      (node (ref "U4") (pin "5") (pinfunction "VOUT_5") (pintype "power_in"))
      (node (ref "VS") (pin "24") (pinfunction "CVCC2_24") (pintype "power_in"))
      (node (ref "VS") (pin "31") (pinfunction "CVCC3_31") (pintype "power_in"))
      (node (ref "VS") (pin "5") (pinfunction "CVCC0_5") (pintype "power_in"))
      (node (ref "VS") (pin "7") (pinfunction "CVCC1_7") (pintype "power_in"))
      (node (ref "VS_C10") (pin "1") (pinfunction "1_1") (pintype "passive"))
      (node (ref "VS_C11") (pin "1") (pinfunction "1_1") (pintype "passive"))
      (node (ref "VS_C12") (pin "1") (pinfunction "1_1") (pintype "passive"))
      (node (ref "VS_C13") (pin "1") (pinfunction "1_1") (pintype "passive"))
    )
    (net (code "2") (name "+2V5") (class "Default")
      (node (ref "ARM") (pin "14") (pinfunction "VCC25_14") (pintype "power_in"))
      (node (ref "ARM") (pin "38") (pinfunction "VCC25_38") (pintype "power_in"))
      (node (ref "ARM") (pin "62") (pinfunction "VCC25_62") (pintype "power_in"))
      (node (ref "ARM") (pin "7") (pinfunction "LDO_7") (pintype "power_in"))
      (node (ref "ARM") (pin "88") (pinfunction "VCC25_88") (pintype "power_in"))
      (node (ref "ARM_C10") (pin "1") (pinfunction "1_1") (pintype "passive"))
      (node (ref "ARM_C11") (pin "1") (pinfunction "1_1") (pintype "passive"))
      (node (ref "ARM_C12") (pin "1") (pinfunction "1_1") (pintype "passive"))
      (node (ref "ARM_C9") (pin "1") (pinfunction "1_1") (pintype "passive"))
    )
    (net (code "3") (name "+2V8") (class "Default")
      (node (ref "C11") (pin "1") (pinfunction "1_1") (pintype "passive"))
      (node (ref "U3") (pin "5") (pinfunction "VOUT_5") (pintype "power_in"))
      (node (ref "VS") (pin "38") (pinfunction "AVCC0_38") (pintype "power_in"))
      (node (ref "VS") (pin "43") (pinfunction "AVCC1_43") (pintype "power_in"))
      (node (ref "VS") (pin "45") (pinfunction "AVCC2_45") (pintype "power_in"))
      (node (ref "VS_C14") (pin "1") (pinfunction "1_1") (pintype "passive"))
      (node (ref "VS_C15") (pin "1") (pinfunction "1_1") (pintype "passive"))
    )
    (net (code "4") (name "+3V3") (class "Default")
      (node (ref "ARM") (pin "20") (pinfunction "VCC_20") (pintype "power_in"))
      (node (ref "ARM") (pin "3") (pinfunction "VCCA_3") (pintype "power_in"))
      (node (ref "ARM") (pin "32") (pinfunction "VCC_32") (pintype "power_in"))
      (node (ref "ARM") (pin "36") (pinfunction "VCCPHY_36") (pintype "power_in"))
      (node (ref "ARM") (pin "44") (pinfunction "VCC_44") (pintype "power_in"))
      (node (ref "ARM") (pin "56") (pinfunction "VCC_56") (pintype "power_in"))
      (node (ref "ARM") (pin "68") (pinfunction "VCC_68") (pintype "power_in"))
      (node (ref "ARM") (pin "8") (pinfunction "VCC_8") (pintype "power_in"))
      (node (ref "ARM") (pin "81") (pinfunction "VCC_81") (pintype "power_in"))
      (node (ref "ARM") (pin "83") (pinfunction "VCCPHY_83") (pintype "power_in"))
      (node (ref "ARM") (pin "84") (pinfunction "VCCPHY_84") (pintype "power_in"))
      (node (ref "ARM") (pin "93") (pinfunction "VCC_93") (pintype "power_in"))
      (node (ref "ARM") (pin "98") (pinfunction "VCCA_98") (pintype "power_in"))
      (node (ref "ARM_C5") (pin "1") (pinfunction "1_1") (pintype "passive"))
      (node (ref "ARM_C6") (pin "1") (pinfunction "1_1") (pintype "passive"))
      (node (ref "ARM_C7") (pin "1") (pinfunction "1_1") (pintype "passive"))
      (node (ref "ARM_C8") (pin "1") (pinfunction "1_1") (pintype "passive"))
      (node (ref "ARM_R1") (pin "1") (pinfunction "1_1") (pintype "passive"))
      (node (ref "ARM_R2") (pin "2") (pinfunction "2_2") (pintype "passive"))
      (node (ref "ARM_R3") (pin "2") (pinfunction "2_2") (pintype "passive"))
      (node (ref "C7") (pin "1") (pinfunction "1_1") (pintype "passive"))
      (node (ref "C8") (pin "1") (pinfunction "1_1") (pintype "passive"))
      (node (ref "EXP") (pin "5") (pinfunction "5_5") (pintype "passive"))
      (node (ref "EXP") (pin "6") (pinfunction "6_6") (pintype "passive"))
      (node (ref "EXP_C2") (pin "2") (pinfunction "2_2") (pintype "passive"))
      (node (ref "FM") (pin "3") (pinfunction "-WP_3") (pintype "input"))
      (node (ref "FM") (pin "7") (pinfunction "-HOLD_7") (pintype "input"))
      (node (ref "FM") (pin "8") (pinfunction "VCC_8") (pintype "power_in"))
      (node (ref "FM_C1") (pin "1") (pinfunction "1_1") (pintype "passive"))
      (node (ref "FM_R1") (pin "2") (pinfunction "2_2") (pintype "passive"))
      (node (ref "JTAG") (pin "1") (pinfunction "1_1") (pintype "passive"))
      (node (ref "PWR") (pin "2") (pinfunction "2_2") (pintype "passive"))
      (node (ref "PWR_C1") (pin "2") (pinfunction "2_2") (pintype "passive"))
      (node (ref "RJ") (pin "3") (pinfunction "RCT_3") (pintype "bidirectional"))
      (node (ref "RJ") (pin "4") (pinfunction "TCT_4") (pintype "bidirectional"))
      (node (ref "RJ") (pin "LED1+") (pinfunction "LED1+_LED1+") (pintype "input"))
      (node (ref "RJ") (pin "LED2+") (pinfunction "LED2+_LED2+") (pintype "input"))
      (node (ref "RJ_C1") (pin "1") (pinfunction "1_1") (pintype "passive"))
      (node (ref "RJ_C3") (pin "2") (pinfunction "2_2") (pintype "passive"))
      (node (ref "RJ_C4") (pin "2") (pinfunction "2_2") (pintype "passive"))
      (node (ref "RJ_C7") (pin "2") (pinfunction "2_2") (pintype "passive"))
      (node (ref "RJ_C8") (pin "2") (pinfunction "2_2") (pintype "passive"))
      (node (ref "RJ_R1") (pin "2") (pinfunction "2_2") (pintype "passive"))
      (node (ref "RJ_R2") (pin "2") (pinfunction "2_2") (pintype "passive"))
      (node (ref "RJ_R3") (pin "2") (pinfunction "2_2") (pintype "passive"))
      (node (ref "RJ_R4") (pin "2") (pinfunction "2_2") (pintype "passive"))
      (node (ref "SD_C2") (pin "2") (pinfunction "2_2") (pintype "passive"))
      (node (ref "SD_C3") (pin "2") (pinfunction "2_2") (pintype "passive"))
      (node (ref "SD_Q1") (pin "2") (pinfunction "S_2") (pintype "passive"))
      (node (ref "SD_R1") (pin "1") (pinfunction "1_1") (pintype "passive"))
      (node (ref "U2") (pin "2") (pinfunction "VO_2") (pintype "passive"))
      (node (ref "VS") (pin "14") (pinfunction "IOVCC1_14") (pintype "power_in"))
      (node (ref "VS") (pin "19") (pinfunction "IOVCC2_19") (pintype "power_in"))
      (node (ref "VS") (pin "26") (pinfunction "RX_26") (pintype "input"))
      (node (ref "VS") (pin "32") (pinfunction "TEST_32") (pintype "input"))
      (node (ref "VS") (pin "6") (pinfunction "IOVCC0_6") (pintype "power_in"))
      (node (ref "VS_C7") (pin "1") (pinfunction "1_1") (pintype "passive"))
      (node (ref "VS_C8") (pin "1") (pinfunction "1_1") (pintype "passive"))
      (node (ref "VS_C9") (pin "1") (pinfunction "1_1") (pintype "passive"))
    )
    (net (code "5") (name "+5V") (class "Default")
      (node (ref "C12") (pin "2") (pinfunction "2_2") (pintype "passive"))
      (node (ref "C4") (pin "+") (pinfunction "+_+") (pintype "passive"))
      (node (ref "C5") (pin "1") (pinfunction "1_1") (pintype "passive"))
      (node (ref "C6") (pin "2") (pinfunction "2_2") (pintype "passive"))
      (node (ref "EXP") (pin "3") (pinfunction "3_3") (pintype "passive"))
      (node (ref "EXP") (pin "4") (pinfunction "4_4") (pintype "passive"))
      (node (ref "EXP_C1") (pin "2") (pinfunction "2_2") (pintype "passive"))
      (node (ref "L1") (pin "2") (pinfunction "2_2") (pintype "passive"))
      (node (ref "L2") (pin "1") (pinfunction "1_1") (pintype "passive"))
      (node (ref "PWR") (pin "1") (pinfunction "1_1") (pintype "passive"))
      (node (ref "PWR_C2") (pin "2") (pinfunction "2_2") (pintype "passive"))
      (node (ref "U1") (pin "4") (pinfunction "FB_4") (pintype "input"))
      (node (ref "U2") (pin "3") (pinfunction "VI_3") (pintype "input"))
      (node (ref "U4") (pin "1") (pinfunction "VIN_1") (pintype "power_in"))
      (node (ref "U4") (pin "3") (pinfunction "ON-~{OFF}_3") (pintype "input"))
      (node (ref "USB_L1") (pin "1") (pinfunction "1_1") (pintype "passive"))
    )
    (net (code "6") (name "7") (class "Default")
      (node (ref "ARM") (pin "47") (pinfunction "PHB0/PF0_47") (pintype "bidirectional"))
      (node (ref "EXP") (pin "7") (pinfunction "7_7") (pintype "passive"))
    )
    (net (code "7") (name "8") (class "Default")
      (node (ref "ARM") (pin "70") (pinfunction "I2C0SCL/PB2_70") (pintype "bidirectional"))
      (node (ref "EXP") (pin "8") (pinfunction "8_8") (pintype "passive"))
    )
    (net (code "8") (name "9") (class "Default")
      (node (ref "ARM") (pin "71") (pinfunction "I2C0SDA/PB3_71") (pintype "bidirectional"))
      (node (ref "EXP") (pin "9") (pinfunction "9_9") (pintype "passive"))
    )
    (net (code "9") (name "13") (class "Default")
      (node (ref "ARM") (pin "90") (pinfunction "C0+/C0O/PB6_90") (pintype "bidirectional"))
      (node (ref "EXP") (pin "13") (pinfunction "13_13") (pintype "passive"))
    )
    (net (code "10") (name "14") (class "Default")
      (node (ref "ARM") (pin "91") (pinfunction "C1-/PB5_91") (pintype "bidirectional"))
      (node (ref "EXP") (pin "14") (pinfunction "14_14") (pintype "passive"))
    )
    (net (code "11") (name "15") (class "Default")
      (node (ref "ARM") (pin "92") (pinfunction "C0-/PB4_92") (pintype "bidirectional"))
      (node (ref "EXP") (pin "15") (pinfunction "15_15") (pintype "passive"))
    )
    (net (code "12") (name "16") (class "Default")
      (node (ref "ARM") (pin "95") (pinfunction "CCP0/PD4_95") (pintype "bidirectional"))
      (node (ref "EXP") (pin "16") (pinfunction "16_16") (pintype "passive"))
    )
    (net (code "13") (name "17") (class "Default")
      (node (ref "ARM") (pin "96") (pinfunction "CCP2/PD5_96") (pintype "bidirectional"))
      (node (ref "EXP") (pin "17") (pinfunction "17_17") (pintype "passive"))
    )
    (net (code "14") (name "18") (class "Default")
      (node (ref "ARM") (pin "99") (pinfunction "FAULT/PD6_99") (pintype "bidirectional"))
      (node (ref "EXP") (pin "18") (pinfunction "18_18") (pintype "passive"))
    )
    (net (code "15") (name "19") (class "Default")
      (node (ref "ARM") (pin "100") (pinfunction "IDX0/PD7_100") (pintype "bidirectional"))
      (node (ref "EXP") (pin "19") (pinfunction "19_19") (pintype "passive"))
    )
    (net (code "16") (name "20") (class "Default")
      (node (ref "ARM") (pin "1") (pinfunction "PWM5/PE7_1") (pintype "bidirectional"))
      (node (ref "EXP") (pin "20") (pinfunction "20_20") (pintype "passive"))
    )
    (net (code "17") (name "21") (class "Default")
      (node (ref "ARM") (pin "2") (pinfunction "PWM4/PE6_2") (pintype "bidirectional"))
      (node (ref "EXP") (pin "21") (pinfunction "21_21") (pintype "passive"))
    )
    (net (code "18") (name "22") (class "Default")
      (node (ref "ARM") (pin "5") (pinfunction "PE5_5") (pintype "bidirectional"))
      (node (ref "EXP") (pin "22") (pinfunction "22_22") (pintype "passive"))
    )
    (net (code "19") (name "23") (class "Default")
      (node (ref "ARM") (pin "6") (pinfunction "CCP3/PE4_6") (pintype "bidirectional"))
      (node (ref "EXP") (pin "23") (pinfunction "23_23") (pintype "passive"))
    )
    (net (code "20") (name "24") (class "Default")
      (node (ref "ARM") (pin "10") (pinfunction "PWM0/PD0_10") (pintype "bidirectional"))
      (node (ref "EXP") (pin "24") (pinfunction "24_24") (pintype "passive"))
    )
    (net (code "21") (name "25") (class "Default")
      (node (ref "ARM") (pin "11") (pinfunction "PHA0/PD1_11") (pintype "bidirectional"))
      (node (ref "EXP") (pin "25") (pinfunction "25_25") (pintype "passive"))
    )
    (net (code "22") (name "26") (class "Default")
      (node (ref "ARM") (pin "12") (pinfunction "U1RX/PD2_12") (pintype "bidirectional"))
      (node (ref "EXP") (pin "26") (pinfunction "26_26") (pintype "passive"))
    )
    (net (code "23") (name "27") (class "Default")
      (node (ref "ARM") (pin "13") (pinfunction "U1TX/PD3_13") (pintype "bidirectional"))
      (node (ref "EXP") (pin "27") (pinfunction "27_27") (pintype "passive"))
    )
    (net (code "24") (name "28") (class "Default")
      (node (ref "ARM") (pin "18") (pinfunction "U2TX/PG1_18") (pintype "bidirectional"))
      (node (ref "EXP") (pin "28") (pinfunction "28_28") (pintype "passive"))
      (node (ref "R2") (pin "1") (pinfunction "1_1") (pintype "passive"))
    )
    (net (code "25") (name "29") (class "Default")
      (node (ref "ARM") (pin "19") (pinfunction "U2RX/PG0_19") (pintype "bidirectional"))
      (node (ref "EXP") (pin "29") (pinfunction "29_29") (pintype "passive"))
      (node (ref "R1") (pin "1") (pinfunction "1_1") (pintype "passive"))
    )
    (net (code "26") (name "30") (class "Default")
      (node (ref "ARM") (pin "22") (pinfunction "C2-/PC7_22") (pintype "bidirectional"))
      (node (ref "EXP") (pin "30") (pinfunction "30_30") (pintype "passive"))
    )
    (net (code "27") (name "31") (class "Default")
      (node (ref "ARM") (pin "23") (pinfunction "C2+/C2O/PC6_23") (pintype "bidirectional"))
      (node (ref "EXP") (pin "31") (pinfunction "31_31") (pintype "passive"))
    )
    (net (code "28") (name "32") (class "Default")
      (node (ref "ARM") (pin "24") (pinfunction "C1+/C1O/PC5_24") (pintype "bidirectional"))
      (node (ref "EXP") (pin "32") (pinfunction "32_32") (pintype "passive"))
    )
    (net (code "29") (name "33") (class "Default")
      (node (ref "ARM") (pin "25") (pinfunction "CCP5/PC4_25") (pintype "bidirectional"))
      (node (ref "EXP") (pin "33") (pinfunction "33_33") (pintype "passive"))
    )
    (net (code "30") (name "AGND") (class "Default")
      (node (ref "C10") (pin "2") (pinfunction "2_2") (pintype "passive"))
      (node (ref "C11") (pin "2") (pinfunction "2_2") (pintype "passive"))
      (node (ref "C9") (pin "1") (pinfunction "1_1") (pintype "passive"))
      (node (ref "U3") (pin "2") (pinfunction "GND_2") (pintype "power_in"))
      (node (ref "VS") (pin "37") (pinfunction "AGND0_37") (pintype "power_in"))
      (node (ref "VS") (pin "40") (pinfunction "AGND1_40") (pintype "power_in"))
      (node (ref "VS") (pin "41") (pinfunction "AGND2_41") (pintype "power_in"))
      (node (ref "VS") (pin "47") (pinfunction "AGND3_47") (pintype "power_in"))
      (node (ref "VS_C14") (pin "2") (pinfunction "2_2") (pintype "passive"))
      (node (ref "VS_C15") (pin "2") (pinfunction "2_2") (pintype "passive"))
      (node (ref "VS_C3") (pin "1") (pinfunction "1_1") (pintype "passive"))
      (node (ref "VS_C4") (pin "1") (pinfunction "1_1") (pintype "passive"))
      (node (ref "VS_C5") (pin "1") (pinfunction "1_1") (pintype "passive"))
      (node (ref "VS_C6") (pin "1") (pinfunction "1_1") (pintype "passive"))
      (node (ref "VS_CL2") (pin "2") (pinfunction "2_2") (pintype "passive"))
      (node (ref "VS_CR2") (pin "2") (pinfunction "2_2") (pintype "passive"))
      (node (ref "VS_GND") (pin "2") (pinfunction "2_2") (pintype "passive"))
      (node (ref "VS_R7") (pin "2") (pinfunction "2_2") (pintype "passive"))
      (node (ref "VS_R8") (pin "2") (pinfunction "2_2") (pintype "passive"))
    )
    (net (code "31") (name "FM_CS") (class "Default")
      (node (ref "ARM") (pin "73") (pinfunction "SSI1FSS/PE1_73") (pintype "bidirectional"))
      (node (ref "FM") (pin "1") (pinfunction "-CS_1") (pintype "input"))
      (node (ref "FM_R1") (pin "1") (pinfunction "1_1") (pintype "passive"))
    )
    (net (code "32") (name "GND") (class "Default")
      (node (ref "ARM") (pin "15") (pinfunction "GND_15") (pintype "power_in"))
      (node (ref "ARM") (pin "21") (pinfunction "GND_21") (pintype "power_in"))
      (node (ref "ARM") (pin "33") (pinfunction "GND_33") (pintype "power_in"))
      (node (ref "ARM") (pin "39") (pinfunction "GND_39") (pintype "power_in"))
      (node (ref "ARM") (pin "4") (pinfunction "GNDA_4") (pintype "power_in"))
      (node (ref "ARM") (pin "42") (pinfunction "GNDPHY_42") (pintype "power_in"))
      (node (ref "ARM") (pin "45") (pinfunction "GND_45") (pintype "power_in"))
      (node (ref "ARM") (pin "50") (pinfunction "~{WAKE}_50") (pintype "input"))
      (node (ref "ARM") (pin "54") (pinfunction "GND_54") (pintype "power_in"))
      (node (ref "ARM") (pin "57") (pinfunction "GND_57") (pintype "power_in"))
      (node (ref "ARM") (pin "63") (pinfunction "GND_63") (pintype "power_in"))
      (node (ref "ARM") (pin "65") (pinfunction "CMOD0_65") (pintype "bidirectional"))
      (node (ref "ARM") (pin "69") (pinfunction "GND_69") (pintype "power_in"))
      (node (ref "ARM") (pin "76") (pinfunction "CMOD1_76") (pintype "bidirectional"))
      (node (ref "ARM") (pin "82") (pinfunction "GND_82") (pintype "power_in"))
      (node (ref "ARM") (pin "85") (pinfunction "GNDPHY_85") (pintype "power_in"))
      (node (ref "ARM") (pin "86") (pinfunction "GNDPHY_86") (pintype "power_in"))
      (node (ref "ARM") (pin "87") (pinfunction "GND_87") (pintype "power_in"))
      (node (ref "ARM") (pin "9") (pinfunction "GND_9") (pintype "power_in"))
      (node (ref "ARM") (pin "94") (pinfunction "GND_94") (pintype "power_in"))
      (node (ref "ARM") (pin "97") (pinfunction "GNDA_97") (pintype "power_in"))
      (node (ref "ARM_C1") (pin "2") (pinfunction "2_2") (pintype "passive"))
      (node (ref "ARM_C10") (pin "2") (pinfunction "2_2") (pintype "passive"))
      (node (ref "ARM_C11") (pin "2") (pinfunction "2_2") (pintype "passive"))
      (node (ref "ARM_C12") (pin "2") (pinfunction "2_2") (pintype "passive"))
      (node (ref "ARM_C2") (pin "2") (pinfunction "2_2") (pintype "passive"))
      (node (ref "ARM_C3") (pin "2") (pinfunction "2_2") (pintype "passive"))
      (node (ref "ARM_C4") (pin "2") (pinfunction "2_2") (pintype "passive"))
      (node (ref "ARM_C5") (pin "2") (pinfunction "2_2") (pintype "passive"))
      (node (ref "ARM_C6") (pin "2") (pinfunction "2_2") (pintype "passive"))
      (node (ref "ARM_C7") (pin "2") (pinfunction "2_2") (pintype "passive"))
      (node (ref "ARM_C8") (pin "2") (pinfunction "2_2") (pintype "passive"))
      (node (ref "ARM_C9") (pin "2") (pinfunction "2_2") (pintype "passive"))
      (node (ref "ARM_R4") (pin "2") (pinfunction "2_2") (pintype "passive"))
      (node (ref "C1") (pin "-") (pinfunction "-_-") (pintype "passive"))
      (node (ref "C12") (pin "1") (pinfunction "1_1") (pintype "passive"))
      (node (ref "C13") (pin "2") (pinfunction "2_2") (pintype "passive"))
      (node (ref "C14") (pin "2") (pinfunction "2_2") (pintype "passive"))
      (node (ref "C2") (pin "2") (pinfunction "2_2") (pintype "passive"))
      (node (ref "C4") (pin "-") (pinfunction "-_-") (pintype "passive"))
      (node (ref "C5") (pin "2") (pinfunction "2_2") (pintype "passive"))
      (node (ref "C6") (pin "1") (pinfunction "1_1") (pintype "passive"))
      (node (ref "C7") (pin "2") (pinfunction "2_2") (pintype "passive"))
      (node (ref "C8") (pin "2") (pinfunction "2_2") (pintype "passive"))
      (node (ref "D1") (pin "A") (pinfunction "A_A") (pintype "passive"))
      (node (ref "EXP") (pin "1") (pinfunction "1_1") (pintype "passive"))
      (node (ref "EXP") (pin "2") (pinfunction "2_2") (pintype "passive"))
      (node (ref "EXP_C1") (pin "1") (pinfunction "1_1") (pintype "passive"))
      (node (ref "EXP_C2") (pin "1") (pinfunction "1_1") (pintype "passive"))
      (node (ref "EXT_PWR") (pin "1") (pinfunction "1_1") (pintype "passive"))
      (node (ref "EXT_PWR") (pin "2") (pinfunction "2_2") (pintype "passive"))
      (node (ref "FM") (pin "4") (pinfunction "GND_4") (pintype "power_in"))
      (node (ref "FM_C1") (pin "2") (pinfunction "2_2") (pintype "passive"))
      (node (ref "JTAG") (pin "10") (pinfunction "10_10") (pintype "passive"))
      (node (ref "JTAG") (pin "12") (pinfunction "12_12") (pintype "passive"))
      (node (ref "JTAG") (pin "14") (pinfunction "14_14") (pintype "passive"))
      (node (ref "JTAG") (pin "16") (pinfunction "16_16") (pintype "passive"))
      (node (ref "JTAG") (pin "18") (pinfunction "18_18") (pintype "passive"))
      (node (ref "JTAG") (pin "20") (pinfunction "20_20") (pintype "passive"))
      (node (ref "JTAG") (pin "4") (pinfunction "4_4") (pintype "passive"))
      (node (ref "JTAG") (pin "6") (pinfunction "6_6") (pintype "passive"))
      (node (ref "JTAG") (pin "8") (pinfunction "8_8") (pintype "passive"))
      (node (ref "POE") (pin "5") (pinfunction "RTN_5") (pintype "output"))
      (node (ref "PWR") (pin "3") (pinfunction "3_3") (pintype "passive"))
      (node (ref "PWR") (pin "4") (pinfunction "4_4") (pintype "passive"))
      (node (ref "PWR_C1") (pin "1") (pinfunction "1_1") (pintype "passive"))
      (node (ref "PWR_C2") (pin "1") (pinfunction "1_1") (pintype "passive"))
      (node (ref "RJ_C1") (pin "2") (pinfunction "2_2") (pintype "passive"))
      (node (ref "RJ_C10") (pin "2") (pinfunction "2_2") (pintype "passive"))
      (node (ref "RJ_C2") (pin "1") (pinfunction "1_1") (pintype "passive"))
      (node (ref "RJ_C3") (pin "1") (pinfunction "1_1") (pintype "passive"))
      (node (ref "RJ_C4") (pin "1") (pinfunction "1_1") (pintype "passive"))
      (node (ref "RJ_C5") (pin "1") (pinfunction "1_1") (pintype "passive"))
      (node (ref "RJ_C6") (pin "1") (pinfunction "1_1") (pintype "passive"))
      (node (ref "RJ_C7") (pin "1") (pinfunction "1_1") (pintype "passive"))
      (node (ref "RJ_C8") (pin "1") (pinfunction "1_1") (pintype "passive"))
      (node (ref "RJ_C9") (pin "1") (pinfunction "1_1") (pintype "passive"))
      (node (ref "SD") (pin "6") (pinfunction "6_6") (pintype "bidirectional"))
      (node (ref "SD_C1") (pin "2") (pinfunction "2_2") (pintype "passive"))
      (node (ref "SD_C2") (pin "1") (pinfunction "1_1") (pintype "passive"))
      (node (ref "SD_C3") (pin "1") (pinfunction "1_1") (pintype "passive"))
      (node (ref "U1") (pin "3") (pinfunction "SGND_3") (pintype "power_in"))
      (node (ref "U1") (pin "6") (pinfunction "GND_6") (pintype "power_in"))
      (node (ref "U2") (pin "1") (pinfunction "GND_1") (pintype "passive"))
      (node (ref "U4") (pin "2") (pinfunction "GND_2") (pintype "power_in"))
      (node (ref "UART2") (pin "1") (pinfunction "1_1") (pintype "passive"))
      (node (ref "USB") (pin "GND") (pinfunction "GND_GND") (pintype "bidirectional"))
      (node (ref "USB_C1") (pin "1") (pinfunction "1_1") (pintype "passive"))
      (node (ref "USB_C2") (pin "2") (pinfunction "2_2") (pintype "passive"))
      (node (ref "USB_C3") (pin "2") (pinfunction "2_2") (pintype "passive"))
      (node (ref "USB_C4") (pin "1") (pinfunction "1_1") (pintype "passive"))
      (node (ref "VS") (pin "16") (pinfunction "GND1_16") (pintype "power_in"))
      (node (ref "VS") (pin "20") (pinfunction "GND2_20") (pintype "power_in"))
      (node (ref "VS") (pin "21") (pinfunction "GND3_21") (pintype "power_in"))
      (node (ref "VS") (pin "22") (pinfunction "GND4_22") (pintype "power_in"))
      (node (ref "VS") (pin "35") (pinfunction "GND5_35") (pintype "power_in"))
      (node (ref "VS") (pin "4") (pinfunction "GND0_4") (pintype "power_in"))
      (node (ref "VS_C1") (pin "2") (pinfunction "2_2") (pintype "passive"))
      (node (ref "VS_C10") (pin "2") (pinfunction "2_2") (pintype "passive"))
      (node (ref "VS_C11") (pin "2") (pinfunction "2_2") (pintype "passive"))
      (node (ref "VS_C12") (pin "2") (pinfunction "2_2") (pintype "passive"))
      (node (ref "VS_C13") (pin "2") (pinfunction "2_2") (pintype "passive"))
      (node (ref "VS_C2") (pin "2") (pinfunction "2_2") (pintype "passive"))
      (node (ref "VS_C7") (pin "2") (pinfunction "2_2") (pintype "passive"))
      (node (ref "VS_C8") (pin "2") (pinfunction "2_2") (pintype "passive"))
      (node (ref "VS_C9") (pin "2") (pinfunction "2_2") (pintype "passive"))
      (node (ref "VS_R10") (pin "2") (pinfunction "2_2") (pintype "passive"))
      (node (ref "VS_R11") (pin "2") (pinfunction "2_2") (pintype "passive"))
      (node (ref "VS_R12") (pin "2") (pinfunction "2_2") (pintype "passive"))
      (node (ref "VS_R2") (pin "1") (pinfunction "1_1") (pintype "passive"))
      (node (ref "VS_R3") (pin "1") (pinfunction "1_1") (pintype "passive"))
      (node (ref "VS_R9") (pin "2") (pinfunction "2_2") (pintype "passive"))
    )
    (net (code "33") (name "I2S_LROUT") (class "Default")
      (node (ref "I2S") (pin "1") (pinfunction "1_1") (pintype "passive"))
      (node (ref "VS") (pin "36") (pinfunction "GPIO4_36") (pintype "bidirectional"))
      (node (ref "VS_R9") (pin "1") (pinfunction "1_1") (pintype "passive"))
    )
    (net (code "34") (name "I2S_MCLK") (class "Default")
      (node (ref "I2S") (pin "2") (pinfunction "2_2") (pintype "passive"))
      (node (ref "VS") (pin "25") (pinfunction "GPIO5_25") (pintype "bidirectional"))
      (node (ref "VS_R10") (pin "1") (pinfunction "1_1") (pintype "passive"))
    )
    (net (code "35") (name "I2S_SCLK") (class "Default")
      (node (ref "I2S") (pin "3") (pinfunction "3_3") (pintype "passive"))
      (node (ref "VS") (pin "11") (pinfunction "GPIO6_11") (pintype "bidirectional"))
      (node (ref "VS_R11") (pin "1") (pinfunction "1_1") (pintype "passive"))
    )
    (net (code "36") (name "I2S_SDATA") (class "Default")
      (node (ref "I2S") (pin "4") (pinfunction "4_4") (pintype "passive"))
      (node (ref "VS") (pin "12") (pinfunction "GPIO7_12") (pintype "bidirectional"))
      (node (ref "VS_R12") (pin "1") (pinfunction "1_1") (pintype "passive"))
    )
    (net (code "37") (name "LED1") (class "Default")
      (node (ref "ARM") (pin "59") (pinfunction "LED0/PF3_59") (pintype "bidirectional"))
      (node (ref "RJ_R5") (pin "2") (pinfunction "2_2") (pintype "passive"))
    )
    (net (code "38") (name "LED2") (class "Default")
      (node (ref "ARM") (pin "60") (pinfunction "LED1/PF2_60") (pintype "bidirectional"))
      (node (ref "RJ_R6") (pin "2") (pinfunction "2_2") (pintype "passive"))
    )
    (net (code "39") (name "NC") (class "Default")
      (node (ref "RJ") (pin "8") (pinfunction "NC_8") (pintype "power_in"))
    )
    (net (code "40") (name "NC_GND(TAIMAG)") (class "Default")
      (node (ref "RJ") (pin "7") (pinfunction "NC_GND(TAIMAG)_7") (pintype "power_in"))
    )
    (net (code "41") (name "Net-(ARM-ERBIAS)") (class "Default")
      (node (ref "ARM") (pin "41") (pinfunction "ERBIAS_41") (pintype "power_in"))
      (node (ref "ARM_R4") (pin "1") (pinfunction "1_1") (pintype "passive"))
    )
    (net (code "42") (name "Net-(ARM-MDIO)") (class "Default")
      (node (ref "ARM") (pin "58") (pinfunction "MDIO_58") (pintype "bidirectional"))
      (node (ref "ARM_R3") (pin "1") (pinfunction "1_1") (pintype "passive"))
    )
    (net (code "43") (name "Net-(ARM-OSC0)") (class "Default")
      (node (ref "ARM") (pin "48") (pinfunction "OSC0_48") (pintype "bidirectional"))
      (node (ref "ARM_C1") (pin "1") (pinfunction "1_1") (pintype "passive"))
      (node (ref "ARM_Q1") (pin "2") (pinfunction "2_2") (pintype "passive"))
    )
    (net (code "44") (name "Net-(ARM-OSC1)") (class "Default")
      (node (ref "ARM") (pin "49") (pinfunction "OSC1_49") (pintype "bidirectional"))
      (node (ref "ARM_C2") (pin "1") (pinfunction "1_1") (pintype "passive"))
      (node (ref "ARM_Q1") (pin "1") (pinfunction "1_1") (pintype "passive"))
    )
    (net (code "45") (name "Net-(ARM-XTALNPHY)") (class "Default")
      (node (ref "ARM") (pin "17") (pinfunction "XTALNPHY_17") (pintype "bidirectional"))
      (node (ref "ARM_C4") (pin "1") (pinfunction "1_1") (pintype "passive"))
      (node (ref "ARM_Q2") (pin "1") (pinfunction "1_1") (pintype "passive"))
    )
    (net (code "46") (name "Net-(ARM-XTALPPHY)") (class "Default")
      (node (ref "ARM") (pin "16") (pinfunction "XTALPPHY_16") (pintype "bidirectional"))
      (node (ref "ARM_C3") (pin "1") (pinfunction "1_1") (pintype "passive"))
      (node (ref "ARM_Q2") (pin "2") (pinfunction "2_2") (pintype "passive"))
    )
    (net (code "47") (name "Net-(ARM-~{RESET})") (class "Default")
      (node (ref "ARM") (pin "64") (pinfunction "~{RESET}_64") (pintype "input"))
      (node (ref "ARM_R1") (pin "2") (pinfunction "2_2") (pintype "passive"))
    )
    (net (code "48") (name "Net-(D2-PadA)") (class "Default")
      (node (ref "D2") (pin "A") (pinfunction "A_A") (pintype "passive"))
      (node (ref "EXT_PWR") (pin "3") (pinfunction "3_3") (pintype "passive"))
    )
    (net (code "49") (name "Net-(D2-PadC)") (class "Default")
      (node (ref "D2") (pin "C") (pinfunction "C_C") (pintype "passive"))
      (node (ref "D3") (pin "C") (pinfunction "C_C") (pintype "passive"))
      (node (ref "FUSE") (pin "1") (pinfunction "1_1") (pintype "passive"))
    )
    (net (code "50") (name "Net-(OUT-Pad1)") (class "Default")
      (node (ref "OUT") (pin "1") (pinfunction "1_1") (pintype "passive"))
      (node (ref "VS_GBUF") (pin "2") (pinfunction "2_2") (pintype "passive"))
      (node (ref "VS_GND") (pin "1") (pinfunction "1_1") (pintype "passive"))
    )
    (net (code "51") (name "Net-(OUT-Pad2)") (class "Default")
      (node (ref "OUT") (pin "2") (pinfunction "2_2") (pintype "passive"))
      (node (ref "OUT") (pin "4") (pinfunction "4_4") (pintype "passive"))
      (node (ref "VS_CL") (pin "2") (pinfunction "2_2") (pintype "passive"))
      (node (ref "VS_R8") (pin "1") (pinfunction "1_1") (pintype "passive"))
    )
    (net (code "52") (name "Net-(OUT-Pad3)") (class "Default")
      (node (ref "OUT") (pin "3") (pinfunction "3_3") (pintype "passive"))
      (node (ref "OUT") (pin "5") (pinfunction "5_5") (pintype "passive"))
      (node (ref "VS_CR") (pin "2") (pinfunction "2_2") (pintype "passive"))
      (node (ref "VS_R7") (pin "1") (pinfunction "1_1") (pintype "passive"))
    )
    (net (code "53") (name "Net-(POE-CLASS)") (class "Default")
      (node (ref "POE") (pin "2") (pinfunction "CLASS_2") (pintype "output"))
      (node (ref "POE_CLA") (pin "2") (pinfunction "2_2") (pintype "passive"))
    )
    (net (code "54") (name "Net-(POE-DET)") (class "Default")
      (node (ref "POE") (pin "3") (pinfunction "DET_3") (pintype "output"))
      (node (ref "POE_DET") (pin "2") (pinfunction "2_2") (pintype "passive"))
    )
    (net (code "55") (name "Net-(POE-ILM)") (class "Default")
      (node (ref "POE") (pin "1") (pinfunction "ILM_1") (pintype "output"))
      (node (ref "POE_ILM") (pin "2") (pinfunction "2_2") (pintype "passive"))
    )
    (net (code "56") (name "Net-(POE-POE-)") (class "Default")
      (node (ref "POE") (pin "4") (pinfunction "POE-_4") (pintype "power_in"))
      (node (ref "POE_C1") (pin "2") (pinfunction "2_2") (pintype "passive"))
      (node (ref "POE_CLA") (pin "1") (pinfunction "1_1") (pintype "passive"))
      (node (ref "POE_D1") (pin "A") (pinfunction "A_A") (pintype "passive"))
      (node (ref "POE_ILM") (pin "1") (pinfunction "1_1") (pintype "passive"))
      (node (ref "RJ") (pin "10") (pinfunction "POE-_10") (pintype "power_in"))
    )
    (net (code "57") (name "Net-(R1-Pad2)") (class "Default")
      (node (ref "R1") (pin "2") (pinfunction "2_2") (pintype "passive"))
      (node (ref "UART2") (pin "4") (pinfunction "4_4") (pintype "passive"))
    )
    (net (code "58") (name "Net-(R2-Pad2)") (class "Default")
      (node (ref "R2") (pin "2") (pinfunction "2_2") (pintype "passive"))
      (node (ref "UART2") (pin "5") (pinfunction "5_5") (pintype "passive"))
    )
    (net (code "59") (name "Net-(RJ-PadLED1-)") (class "Default")
      (node (ref "RJ") (pin "LED1-") (pinfunction "LED1-_LED1-") (pintype "input"))
      (node (ref "RJ_R5") (pin "1") (pinfunction "1_1") (pintype "passive"))
    )
    (net (code "60") (name "Net-(RJ-PadLED2-)") (class "Default")
      (node (ref "RJ") (pin "LED2-") (pinfunction "LED2-_LED2-") (pintype "input"))
      (node (ref "RJ_R6") (pin "1") (pinfunction "1_1") (pintype "passive"))
    )
    (net (code "61") (name "Net-(RJ-SHIELD-PadNC0)") (class "Default")
      (node (ref "RJ") (pin "NC0") (pinfunction "SHIELD_NC0") (pintype "power_in"))
      (node (ref "RJ") (pin "NC1") (pinfunction "SHIELD_NC1") (pintype "power_in"))
      (node (ref "RJ_R7") (pin "2") (pinfunction "2_2") (pintype "passive"))
    )
    (net (code "62") (name "Net-(RJ_C10-Pad1)") (class "Default")
      (node (ref "RJ_C10") (pin "1") (pinfunction "1_1") (pintype "passive"))
      (node (ref "RJ_R7") (pin "1") (pinfunction "1_1") (pintype "passive"))
    )
    (net (code "63") (name "Net-(SD-Pad1)") (class "Default")
      (node (ref "SD") (pin "1") (pinfunction "1_1") (pintype "bidirectional"))
      (node (ref "SD_R5") (pin "2") (pinfunction "2_2") (pintype "passive"))
    )
    (net (code "64") (name "Net-(SD-Pad8)") (class "Default")
      (node (ref "SD") (pin "8") (pinfunction "8_8") (pintype "bidirectional"))
      (node (ref "SD_R2") (pin "2") (pinfunction "2_2") (pintype "passive"))
    )
    (net (code "65") (name "Net-(SD_Q1-D)") (class "Default")
      (node (ref "SD") (pin "4") (pinfunction "4_4") (pintype "bidirectional"))
      (node (ref "SD_C1") (pin "1") (pinfunction "1_1") (pintype "passive"))
      (node (ref "SD_Q1") (pin "3") (pinfunction "D_3") (pintype "passive"))
      (node (ref "SD_R2") (pin "1") (pinfunction "1_1") (pintype "passive"))
      (node (ref "SD_R3") (pin "1") (pinfunction "1_1") (pintype "passive"))
      (node (ref "SD_R4") (pin "1") (pinfunction "1_1") (pintype "passive"))
      (node (ref "SD_R5") (pin "1") (pinfunction "1_1") (pintype "passive"))
    )
    (net (code "66") (name "Net-(U1-BST)") (class "Default")
      (node (ref "C3") (pin "1") (pinfunction "1_1") (pintype "passive"))
      (node (ref "U1") (pin "1") (pinfunction "BST_1") (pintype "power_in"))
    )
    (net (code "67") (name "Net-(U1-OUT)") (class "Default")
      (node (ref "C3") (pin "2") (pinfunction "2_2") (pintype "passive"))
      (node (ref "D1") (pin "C") (pinfunction "C_C") (pintype "passive"))
      (node (ref "L1") (pin "1") (pinfunction "1_1") (pintype "passive"))
      (node (ref "U1") (pin "8") (pinfunction "OUT_8") (pintype "power_in"))
    )
    (net (code "68") (name "Net-(U1-VD)") (class "Default")
      (node (ref "C2") (pin "1") (pinfunction "1_1") (pintype "passive"))
      (node (ref "U1") (pin "2") (pinfunction "VD_2") (pintype "input"))
    )
    (net (code "69") (name "Net-(U3-BYPASS)") (class "Default")
      (node (ref "C10") (pin "1") (pinfunction "1_1") (pintype "passive"))
      (node (ref "U3") (pin "4") (pinfunction "BYPASS_4") (pintype "input"))
    )
    (net (code "70") (name "Net-(U3-ON-~{OFF})") (class "Default")
      (node (ref "C9") (pin "2") (pinfunction "2_2") (pintype "passive"))
      (node (ref "L2") (pin "2") (pinfunction "2_2") (pintype "passive"))
      (node (ref "U3") (pin "1") (pinfunction "VIN_1") (pintype "power_in"))
      (node (ref "U3") (pin "3") (pinfunction "ON-~{OFF}_3") (pintype "input"))
    )
    (net (code "71") (name "Net-(U4-BYPASS)") (class "Default")
      (node (ref "C13") (pin "1") (pinfunction "1_1") (pintype "passive"))
      (node (ref "U4") (pin "4") (pinfunction "BYPASS_4") (pintype "input"))
    )
    (net (code "72") (name "Net-(USB_Q1-D)") (class "Default")
      (node (ref "USB") (pin "VBUS") (pinfunction "VBUS_VBUS") (pintype "bidirectional"))
      (node (ref "USB_C2") (pin "1") (pinfunction "1_1") (pintype "passive"))
      (node (ref "USB_C3") (pin "1") (pinfunction "1_1") (pintype "passive"))
      (node (ref "USB_Q1") (pin "3") (pinfunction "D_3") (pintype "passive"))
    )
    (net (code "73") (name "Net-(USB_Q1-G)") (class "Default")
      (node (ref "USB_C1") (pin "2") (pinfunction "2_2") (pintype "passive"))
      (node (ref "USB_Q1") (pin "1") (pinfunction "G_1") (pintype "passive"))
      (node (ref "USB_R1") (pin "2") (pinfunction "2_2") (pintype "passive"))
      (node (ref "USB_R2") (pin "1") (pinfunction "1_1") (pintype "passive"))
    )
    (net (code "74") (name "Net-(USB_Q1-S)") (class "Default")
      (node (ref "USB_C4") (pin "2") (pinfunction "2_2") (pintype "passive"))
      (node (ref "USB_L1") (pin "2") (pinfunction "2_2") (pintype "passive"))
      (node (ref "USB_Q1") (pin "2") (pinfunction "S_2") (pintype "passive"))
      (node (ref "USB_R1") (pin "1") (pinfunction "1_1") (pintype "passive"))
    )
    (net (code "75") (name "Net-(VS-GBUF)") (class "Default")
      (node (ref "VS") (pin "42") (pinfunction "GBUF_42") (pintype "passive"))
      (node (ref "VS_GBUF") (pin "1") (pinfunction "1_1") (pintype "passive"))
      (node (ref "VS_R6") (pin "2") (pinfunction "2_2") (pintype "passive"))
    )
    (net (code "76") (name "Net-(VS-GPIO0)") (class "Default")
      (node (ref "VS") (pin "33") (pinfunction "GPIO0_33") (pintype "bidirectional"))
      (node (ref "VS") (pin "34") (pinfunction "GPIO1_34") (pintype "bidirectional"))
      (node (ref "VS_R3") (pin "2") (pinfunction "2_2") (pintype "passive"))
    )
    (net (code "77") (name "Net-(VS-GPIO2)") (class "Default")
      (node (ref "VS") (pin "10") (pinfunction "GPIO3_10") (pintype "bidirectional"))
      (node (ref "VS") (pin "9") (pinfunction "GPIO2_9") (pintype "bidirectional"))
      (node (ref "VS_R2") (pin "2") (pinfunction "2_2") (pintype "passive"))
    )
    (net (code "78") (name "Net-(VS-LEFT)") (class "Default")
      (node (ref "VS") (pin "46") (pinfunction "LEFT_46") (pintype "passive"))
      (node (ref "VS_R4") (pin "2") (pinfunction "2_2") (pintype "passive"))
      (node (ref "VS_RL") (pin "1") (pinfunction "1_1") (pintype "passive"))
    )
    (net (code "79") (name "Net-(VS-RCAP)") (class "Default")
      (node (ref "VS") (pin "44") (pinfunction "RCAP_44") (pintype "passive"))
      (node (ref "VS_C6") (pin "2") (pinfunction "2_2") (pintype "passive"))
    )
    (net (code "80") (name "Net-(VS-RIGHT)") (class "Default")
      (node (ref "VS") (pin "39") (pinfunction "RIGHT_39") (pintype "passive"))
      (node (ref "VS_R5") (pin "2") (pinfunction "2_2") (pintype "passive"))
      (node (ref "VS_RR") (pin "1") (pinfunction "1_1") (pintype "passive"))
    )
    (net (code "81") (name "Net-(VS-XTALI)") (class "Default")
      (node (ref "VS") (pin "18") (pinfunction "XTALI_18") (pintype "passive"))
      (node (ref "VS_C2") (pin "1") (pinfunction "1_1") (pintype "passive"))
      (node (ref "VS_Q1") (pin "1") (pinfunction "1_1") (pintype "passive"))
      (node (ref "VS_R1") (pin "2") (pinfunction "2_2") (pintype "passive"))
    )
    (net (code "82") (name "Net-(VS-XTALO)") (class "Default")
      (node (ref "VS") (pin "17") (pinfunction "XTALO_17") (pintype "passive"))
      (node (ref "VS_C1") (pin "1") (pinfunction "1_1") (pintype "passive"))
      (node (ref "VS_Q1") (pin "2") (pinfunction "2_2") (pintype "passive"))
      (node (ref "VS_R1") (pin "1") (pinfunction "1_1") (pintype "passive"))
    )
    (net (code "83") (name "Net-(VS_C3-Pad2)") (class "Default")
      (node (ref "VS_C3") (pin "2") (pinfunction "2_2") (pintype "passive"))
      (node (ref "VS_R4") (pin "1") (pinfunction "1_1") (pintype "passive"))
    )
    (net (code "84") (name "Net-(VS_C4-Pad2)") (class "Default")
      (node (ref "VS_C4") (pin "2") (pinfunction "2_2") (pintype "passive"))
      (node (ref "VS_R5") (pin "1") (pinfunction "1_1") (pintype "passive"))
    )
    (net (code "85") (name "Net-(VS_C5-Pad2)") (class "Default")
      (node (ref "VS_C5") (pin "2") (pinfunction "2_2") (pintype "passive"))
      (node (ref "VS_R6") (pin "1") (pinfunction "1_1") (pintype "passive"))
    )
    (net (code "86") (name "Net-(VS_CL-Pad1)") (class "Default")
      (node (ref "VS_CL") (pin "1") (pinfunction "1_1") (pintype "passive"))
      (node (ref "VS_CL2") (pin "1") (pinfunction "1_1") (pintype "passive"))
      (node (ref "VS_RL") (pin "2") (pinfunction "2_2") (pintype "passive"))
    )
    (net (code "87") (name "Net-(VS_CR-Pad1)") (class "Default")
      (node (ref "VS_CR") (pin "1") (pinfunction "1_1") (pintype "passive"))
      (node (ref "VS_CR2") (pin "1") (pinfunction "1_1") (pintype "passive"))
      (node (ref "VS_RR") (pin "2") (pinfunction "2_2") (pintype "passive"))
    )
    (net (code "88") (name "POE+") (class "Default")
      (node (ref "D3") (pin "A") (pinfunction "A_A") (pintype "passive"))
      (node (ref "RJ") (pin "9") (pinfunction "POE+_9") (pintype "power_in"))
    )
    (net (code "89") (name "PWR+") (class "Default")
      (node (ref "C1") (pin "+") (pinfunction "+_+") (pintype "passive"))
      (node (ref "FUSE") (pin "2") (pinfunction "2_2") (pintype "passive"))
      (node (ref "POE") (pin "8") (pinfunction "POE+_8") (pintype "power_in"))
      (node (ref "POE_C1") (pin "1") (pinfunction "1_1") (pintype "passive"))
      (node (ref "POE_D1") (pin "C") (pinfunction "C_C") (pintype "passive"))
      (node (ref "POE_DET") (pin "1") (pinfunction "1_1") (pintype "passive"))
      (node (ref "U1") (pin "5") (pinfunction "ON/~{OFF}_5") (pintype "input"))
      (node (ref "U1") (pin "7") (pinfunction "VIN_7") (pintype "power_in"))
    )
    (net (code "90") (name "RD+") (class "Default")
      (node (ref "ARM") (pin "40") (pinfunction "RXIP_40") (pintype "bidirectional"))
      (node (ref "RJ") (pin "1") (pinfunction "RD+_1") (pintype "bidirectional"))
      (node (ref "RJ_C2") (pin "2") (pinfunction "2_2") (pintype "passive"))
      (node (ref "RJ_R1") (pin "1") (pinfunction "1_1") (pintype "passive"))
    )
    (net (code "91") (name "RD-") (class "Default")
      (node (ref "ARM") (pin "37") (pinfunction "RXIN_37") (pintype "bidirectional"))
      (node (ref "RJ") (pin "2") (pinfunction "RD-_2") (pintype "bidirectional"))
      (node (ref "RJ_C5") (pin "2") (pinfunction "2_2") (pintype "passive"))
      (node (ref "RJ_R2") (pin "1") (pinfunction "1_1") (pintype "passive"))
    )
    (net (code "92") (name "SCK") (class "Default")
      (node (ref "ARM") (pin "72") (pinfunction "SSI1CLK/PE0_72") (pintype "bidirectional"))
      (node (ref "EXP") (pin "10") (pinfunction "10_10") (pintype "passive"))
      (node (ref "FM") (pin "6") (pinfunction "CLK_6") (pintype "input"))
      (node (ref "SD") (pin "5") (pinfunction "5_5") (pintype "bidirectional"))
    )
    (net (code "93") (name "SD_CS") (class "Default")
      (node (ref "ARM") (pin "67") (pinfunction "PWM3/PB1_67") (pintype "bidirectional"))
      (node (ref "SD") (pin "2") (pinfunction "2_2") (pintype "bidirectional"))
      (node (ref "SD_R4") (pin "2") (pinfunction "2_2") (pintype "passive"))
    )
    (net (code "94") (name "SD_PWR") (class "Default")
      (node (ref "ARM") (pin "66") (pinfunction "PWM2/PB0_66") (pintype "bidirectional"))
      (node (ref "SD_Q1") (pin "1") (pinfunction "G_1") (pintype "passive"))
      (node (ref "SD_R1") (pin "2") (pinfunction "2_2") (pintype "passive"))
    )
    (net (code "95") (name "SI") (class "Default")
      (node (ref "ARM") (pin "75") (pinfunction "SSI1TX/PE3_75") (pintype "bidirectional"))
      (node (ref "EXP") (pin "12") (pinfunction "12_12") (pintype "passive"))
      (node (ref "FM") (pin "5") (pinfunction "DI_5") (pintype "input"))
      (node (ref "SD") (pin "3") (pinfunction "3_3") (pintype "bidirectional"))
    )
    (net (code "96") (name "SO") (class "Default")
      (node (ref "ARM") (pin "74") (pinfunction "SSI1RX/PE2_74") (pintype "bidirectional"))
      (node (ref "EXP") (pin "11") (pinfunction "11_11") (pintype "passive"))
      (node (ref "FM") (pin "2") (pinfunction "DO_2") (pintype "output"))
      (node (ref "SD") (pin "7") (pinfunction "7_7") (pintype "bidirectional"))
      (node (ref "SD_R3") (pin "2") (pinfunction "2_2") (pintype "passive"))
    )
    (net (code "97") (name "TCK") (class "Default")
      (node (ref "ARM") (pin "80") (pinfunction "TCK/SWCLK/PC0_80") (pintype "bidirectional"))
      (node (ref "JTAG") (pin "9") (pinfunction "9_9") (pintype "passive"))
    )
    (net (code "98") (name "TD+") (class "Default")
      (node (ref "ARM") (pin "43") (pinfunction "TXOP_43") (pintype "bidirectional"))
      (node (ref "RJ") (pin "5") (pinfunction "TD+_5") (pintype "bidirectional"))
      (node (ref "RJ_C6") (pin "2") (pinfunction "2_2") (pintype "passive"))
      (node (ref "RJ_R3") (pin "1") (pinfunction "1_1") (pintype "passive"))
    )
    (net (code "99") (name "TD-") (class "Default")
      (node (ref "ARM") (pin "46") (pinfunction "TXON_46") (pintype "bidirectional"))
      (node (ref "RJ") (pin "6") (pinfunction "TD-_6") (pintype "bidirectional"))
      (node (ref "RJ_C9") (pin "2") (pinfunction "2_2") (pintype "passive"))
      (node (ref "RJ_R4") (pin "1") (pinfunction "1_1") (pintype "passive"))
    )
    (net (code "100") (name "TDI") (class "Default")
      (node (ref "ARM") (pin "78") (pinfunction "TDI/PC2_78") (pintype "bidirectional"))
      (node (ref "JTAG") (pin "5") (pinfunction "5_5") (pintype "passive"))
    )
    (net (code "101") (name "TDO") (class "Default")
      (node (ref "ARM") (pin "77") (pinfunction "TDO/SWO/PC3_77") (pintype "bidirectional"))
      (node (ref "JTAG") (pin "13") (pinfunction "13_13") (pintype "passive"))
    )
    (net (code "102") (name "TMS") (class "Default")
      (node (ref "ARM") (pin "79") (pinfunction "TMS/SWDIO/PC1_79") (pintype "bidirectional"))
      (node (ref "JTAG") (pin "7") (pinfunction "7_7") (pintype "passive"))
    )
    (net (code "103") (name "TRST") (class "Default")
      (node (ref "ARM") (pin "89") (pinfunction "TRST/PB7_89") (pintype "bidirectional"))
      (node (ref "ARM_R2") (pin "1") (pinfunction "1_1") (pintype "passive"))
      (node (ref "JTAG") (pin "3") (pinfunction "3_3") (pintype "passive"))
    )
    (net (code "104") (name "USB_PWR") (class "Default")
      (node (ref "ARM") (pin "61") (pinfunction "PWM1/PF1_61") (pintype "bidirectional"))
      (node (ref "USB_R2") (pin "2") (pinfunction "2_2") (pintype "passive"))
    )
    (net (code "105") (name "VBAT") (class "Default")
      (node (ref "ARM") (pin "55") (pinfunction "VBAT_55") (pintype "power_in"))
    )
    (net (code "106") (name "VS_CS") (class "Default")
      (node (ref "ARM") (pin "34") (pinfunction "CCP1/PA6_34") (pintype "bidirectional"))
      (node (ref "VS") (pin "23") (pinfunction "~{CS}_23") (pintype "input"))
    )
    (net (code "107") (name "VS_DCS") (class "Default")
      (node (ref "ARM") (pin "29") (pinfunction "SSI0FSS/PA3_29") (pintype "bidirectional"))
      (node (ref "VS") (pin "13") (pinfunction "~{DCS}_13") (pintype "input"))
    )
    (net (code "108") (name "VS_DREQ") (class "Default")
      (node (ref "ARM") (pin "27") (pinfunction "U0TX/PA1_27") (pintype "bidirectional"))
      (node (ref "VS") (pin "8") (pinfunction "~{DREQ}_8") (pintype "input"))
    )
    (net (code "109") (name "VS_RST") (class "Default")
      (node (ref "ARM") (pin "35") (pinfunction "CCP4/PA7_35") (pintype "bidirectional"))
      (node (ref "VS") (pin "3") (pinfunction "~{RESET}_3") (pintype "input"))
    )
    (net (code "110") (name "VS_SCK") (class "Default")
      (node (ref "ARM") (pin "28") (pinfunction "SSI0CLK/PA2_28") (pintype "bidirectional"))
      (node (ref "VS") (pin "28") (pinfunction "SCLK_28") (pintype "input"))
    )
    (net (code "111") (name "VS_SI") (class "Default")
      (node (ref "ARM") (pin "31") (pinfunction "SSI0TX/PA5_31") (pintype "bidirectional"))
      (node (ref "VS") (pin "29") (pinfunction "SI_29") (pintype "input"))
    )
    (net (code "112") (name "VS_SO") (class "Default")
      (node (ref "ARM") (pin "30") (pinfunction "SSI0RX/PA4_30") (pintype "bidirectional"))
      (node (ref "VS") (pin "30") (pinfunction "SO_30") (pintype "output"))
    )
    (net (code "113") (name "unconnected-(ARM-U0RX{slash}PA0-Pad26)") (class "Default")
      (node (ref "ARM") (pin "26") (pinfunction "U0RX/PA0_26") (pintype "bidirectional"))
    )
    (net (code "114") (name "unconnected-(ARM-XOSC0-Pad52)") (class "Default")
      (node (ref "ARM") (pin "52") (pinfunction "XOSC0_52") (pintype "bidirectional"))
    )
    (net (code "115") (name "unconnected-(ARM-XOSC1-Pad53)") (class "Default")
      (node (ref "ARM") (pin "53") (pinfunction "XOSC1_53") (pintype "bidirectional"))
    )
    (net (code "116") (name "unconnected-(ARM-~{HIB}-Pad51)") (class "Default")
      (node (ref "ARM") (pin "51") (pinfunction "~{HIB}_51") (pintype "output"))
    )
    (net (code "117") (name "unconnected-(EXP-Pad34)") (class "Default")
      (node (ref "EXP") (pin "34") (pinfunction "34_34") (pintype "passive"))
    )
    (net (code "118") (name "unconnected-(JTAG-Pad2)") (class "Default")
      (node (ref "JTAG") (pin "2") (pinfunction "2_2") (pintype "passive"))
    )
    (net (code "119") (name "unconnected-(JTAG-Pad11)") (class "Default")
      (node (ref "JTAG") (pin "11") (pinfunction "11_11") (pintype "passive"))
    )
    (net (code "120") (name "unconnected-(JTAG-Pad15)") (class "Default")
      (node (ref "JTAG") (pin "15") (pinfunction "15_15") (pintype "passive"))
    )
    (net (code "121") (name "unconnected-(JTAG-Pad17)") (class "Default")
      (node (ref "JTAG") (pin "17") (pinfunction "17_17") (pintype "passive"))
    )
    (net (code "122") (name "unconnected-(JTAG-Pad19)") (class "Default")
      (node (ref "JTAG") (pin "19") (pinfunction "19_19") (pintype "passive"))
    )
    (net (code "123") (name "unconnected-(POE-PG-Pad6)") (class "Default")
      (node (ref "POE") (pin "6") (pinfunction "PG_6") (pintype "output"))
    )
    (net (code "124") (name "unconnected-(SD-SW1-PadK1)") (class "Default")
      (node (ref "SD") (pin "K1") (pinfunction "SW1_K1") (pintype "bidirectional"))
    )
    (net (code "125") (name "unconnected-(SD-SW2-PadK2)") (class "Default")
      (node (ref "SD") (pin "K2") (pinfunction "SW2_K2") (pintype "bidirectional"))
    )
    (net (code "126") (name "unconnected-(UART2-Pad2)") (class "Default")
      (node (ref "UART2") (pin "2") (pinfunction "2_2") (pintype "passive"))
    )
    (net (code "127") (name "unconnected-(UART2-Pad3)") (class "Default")
      (node (ref "UART2") (pin "3") (pinfunction "3_3") (pintype "passive"))
    )
    (net (code "128") (name "unconnected-(UART2-Pad6)") (class "Default")
      (node (ref "UART2") (pin "6") (pinfunction "6_6") (pintype "passive"))
    )
    (net (code "129") (name "unconnected-(USB-PadD+)") (class "Default")
      (node (ref "USB") (pin "D+") (pinfunction "D+_D+") (pintype "bidirectional"))
    )
    (net (code "130") (name "unconnected-(USB-PadD-)") (class "Default")
      (node (ref "USB") (pin "D-") (pinfunction "D-_D-") (pintype "bidirectional"))
    )
    (net (code "131") (name "unconnected-(VS-LINE2-Pad48)") (class "Default")
      (node (ref "VS") (pin "48") (pinfunction "LINE2_48") (pintype "passive"))
    )
    (net (code "132") (name "unconnected-(VS-MIC+{slash}LINE1-Pad1)") (class "Default")
      (node (ref "VS") (pin "1") (pinfunction "MIC+/LINE1_1") (pintype "passive"))
    )
    (net (code "133") (name "unconnected-(VS-MIC--Pad2)") (class "Default")
      (node (ref "VS") (pin "2") (pinfunction "MIC-_2") (pintype "passive"))
    )
    (net (code "134") (name "unconnected-(VS-TX-Pad27)") (class "Default")
      (node (ref "VS") (pin "27") (pinfunction "TX_27") (pintype "output"))
    )
    (net (code "135") (name "unconnected-(VS-VCO-Pad15)") (class "Default")
      (node (ref "VS") (pin "15") (pinfunction "VCO_15") (pintype "output"))
    )
    (net (code "136") (name "unconnected-(X1-Pad1)") (class "Default")
      (node (ref "X1") (pin "1") (pinfunction "1_1") (pintype "passive"))
    )
    (net (code "137") (name "unconnected-(X2-Pad1)") (class "Default")
      (node (ref "X2") (pin "1") (pinfunction "1_1") (pintype "passive"))
    )
    (net (code "138") (name "unconnected-(X3-Pad1)") (class "Default")
      (node (ref "X3") (pin "1") (pinfunction "1_1") (pintype "passive"))
    )
    (net (code "139") (name "unconnected-(X4-Pad1)") (class "Default")
      (node (ref "X4") (pin "1") (pinfunction "1_1") (pintype "passive"))
    )
  )
)
